# SCX3.net
KiCad netlist of a schematic drawn in EAGLE
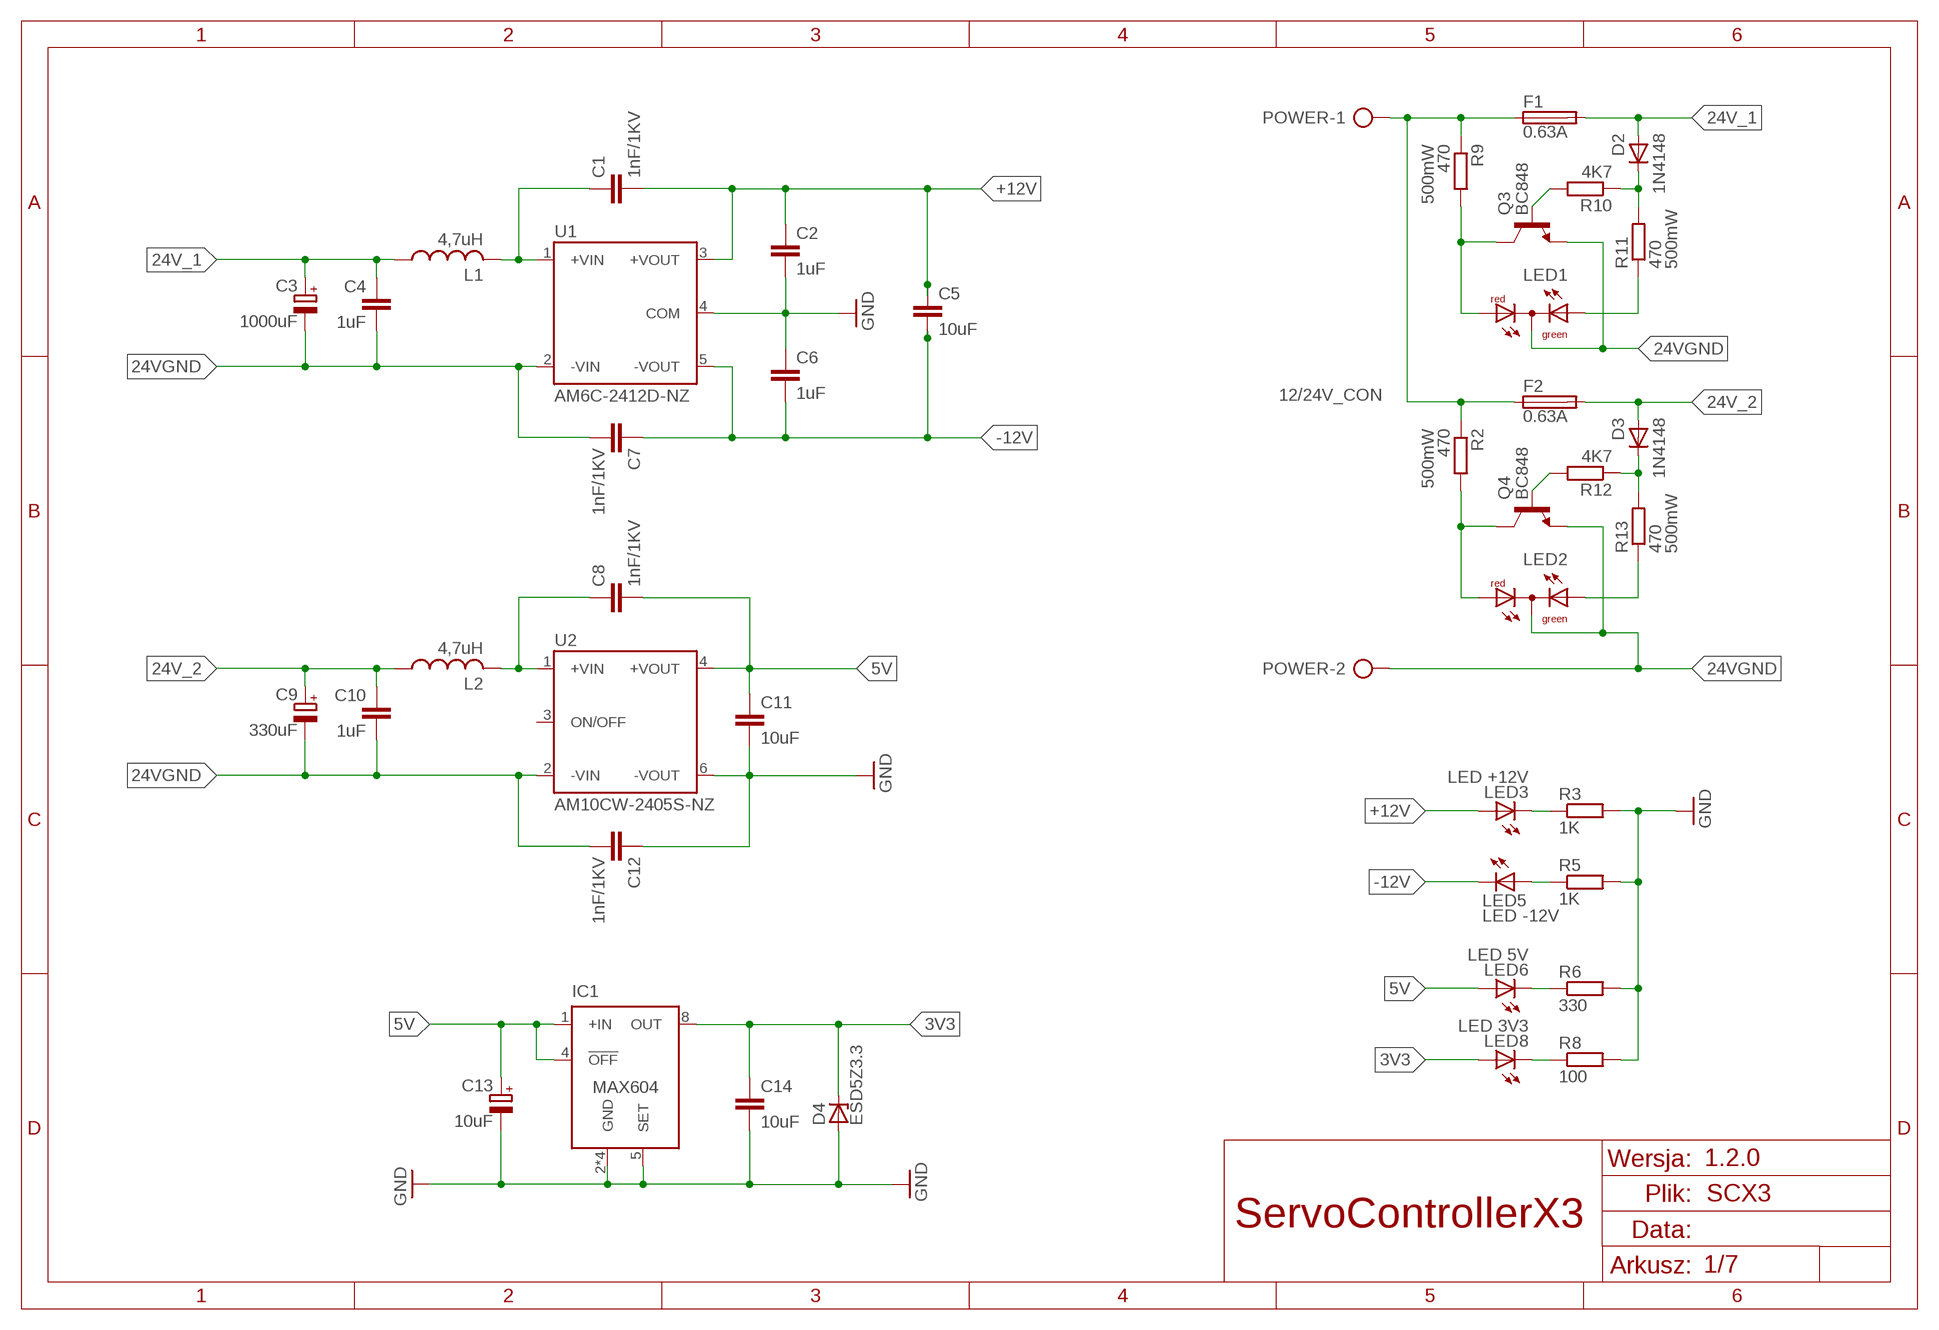
[diagram p0: schematic, sheet 1]
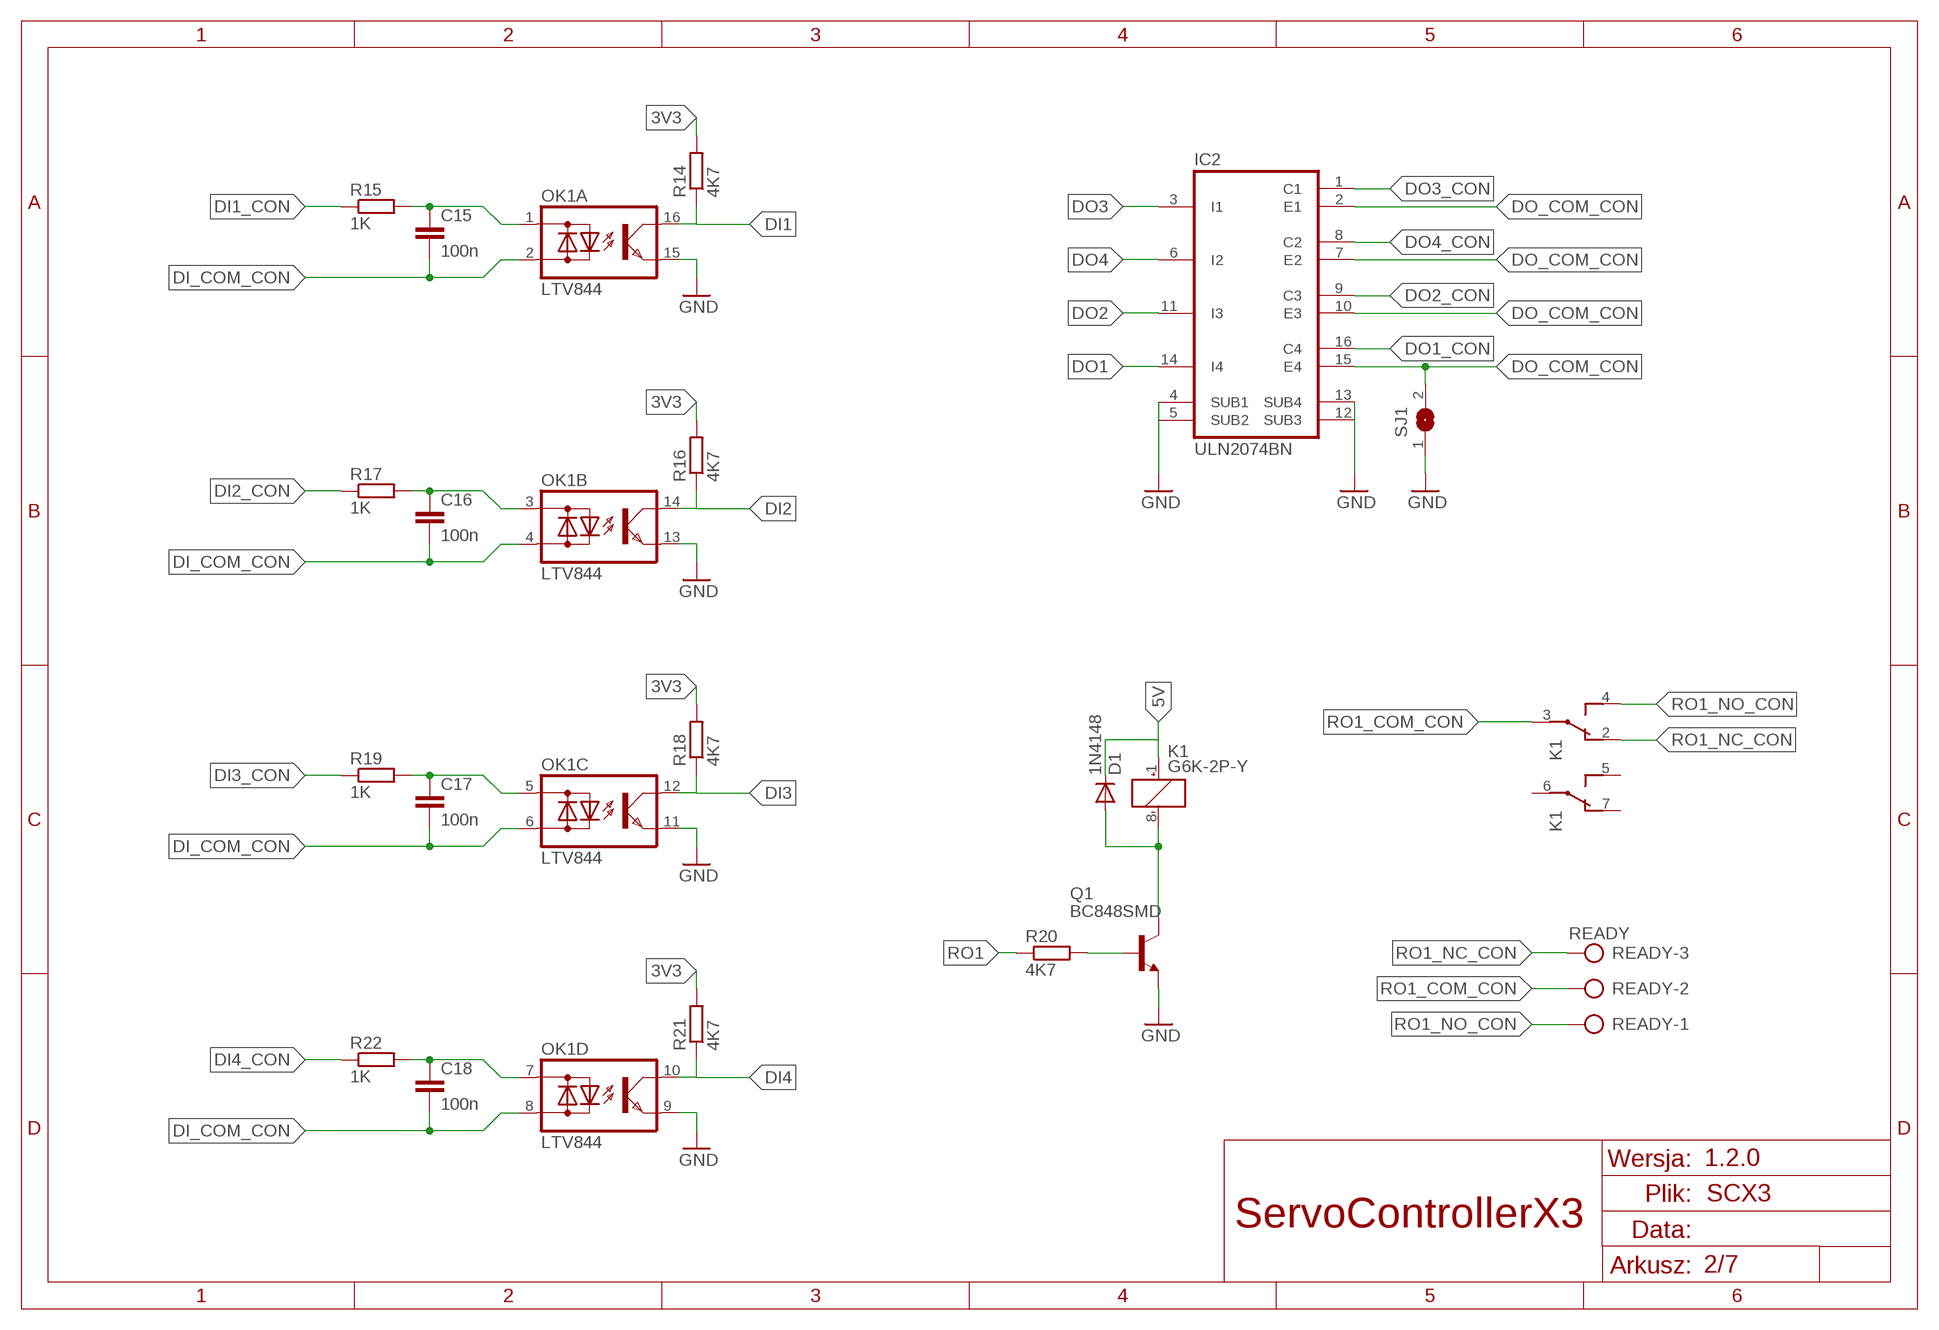
[diagram p1: schematic, sheet 2]
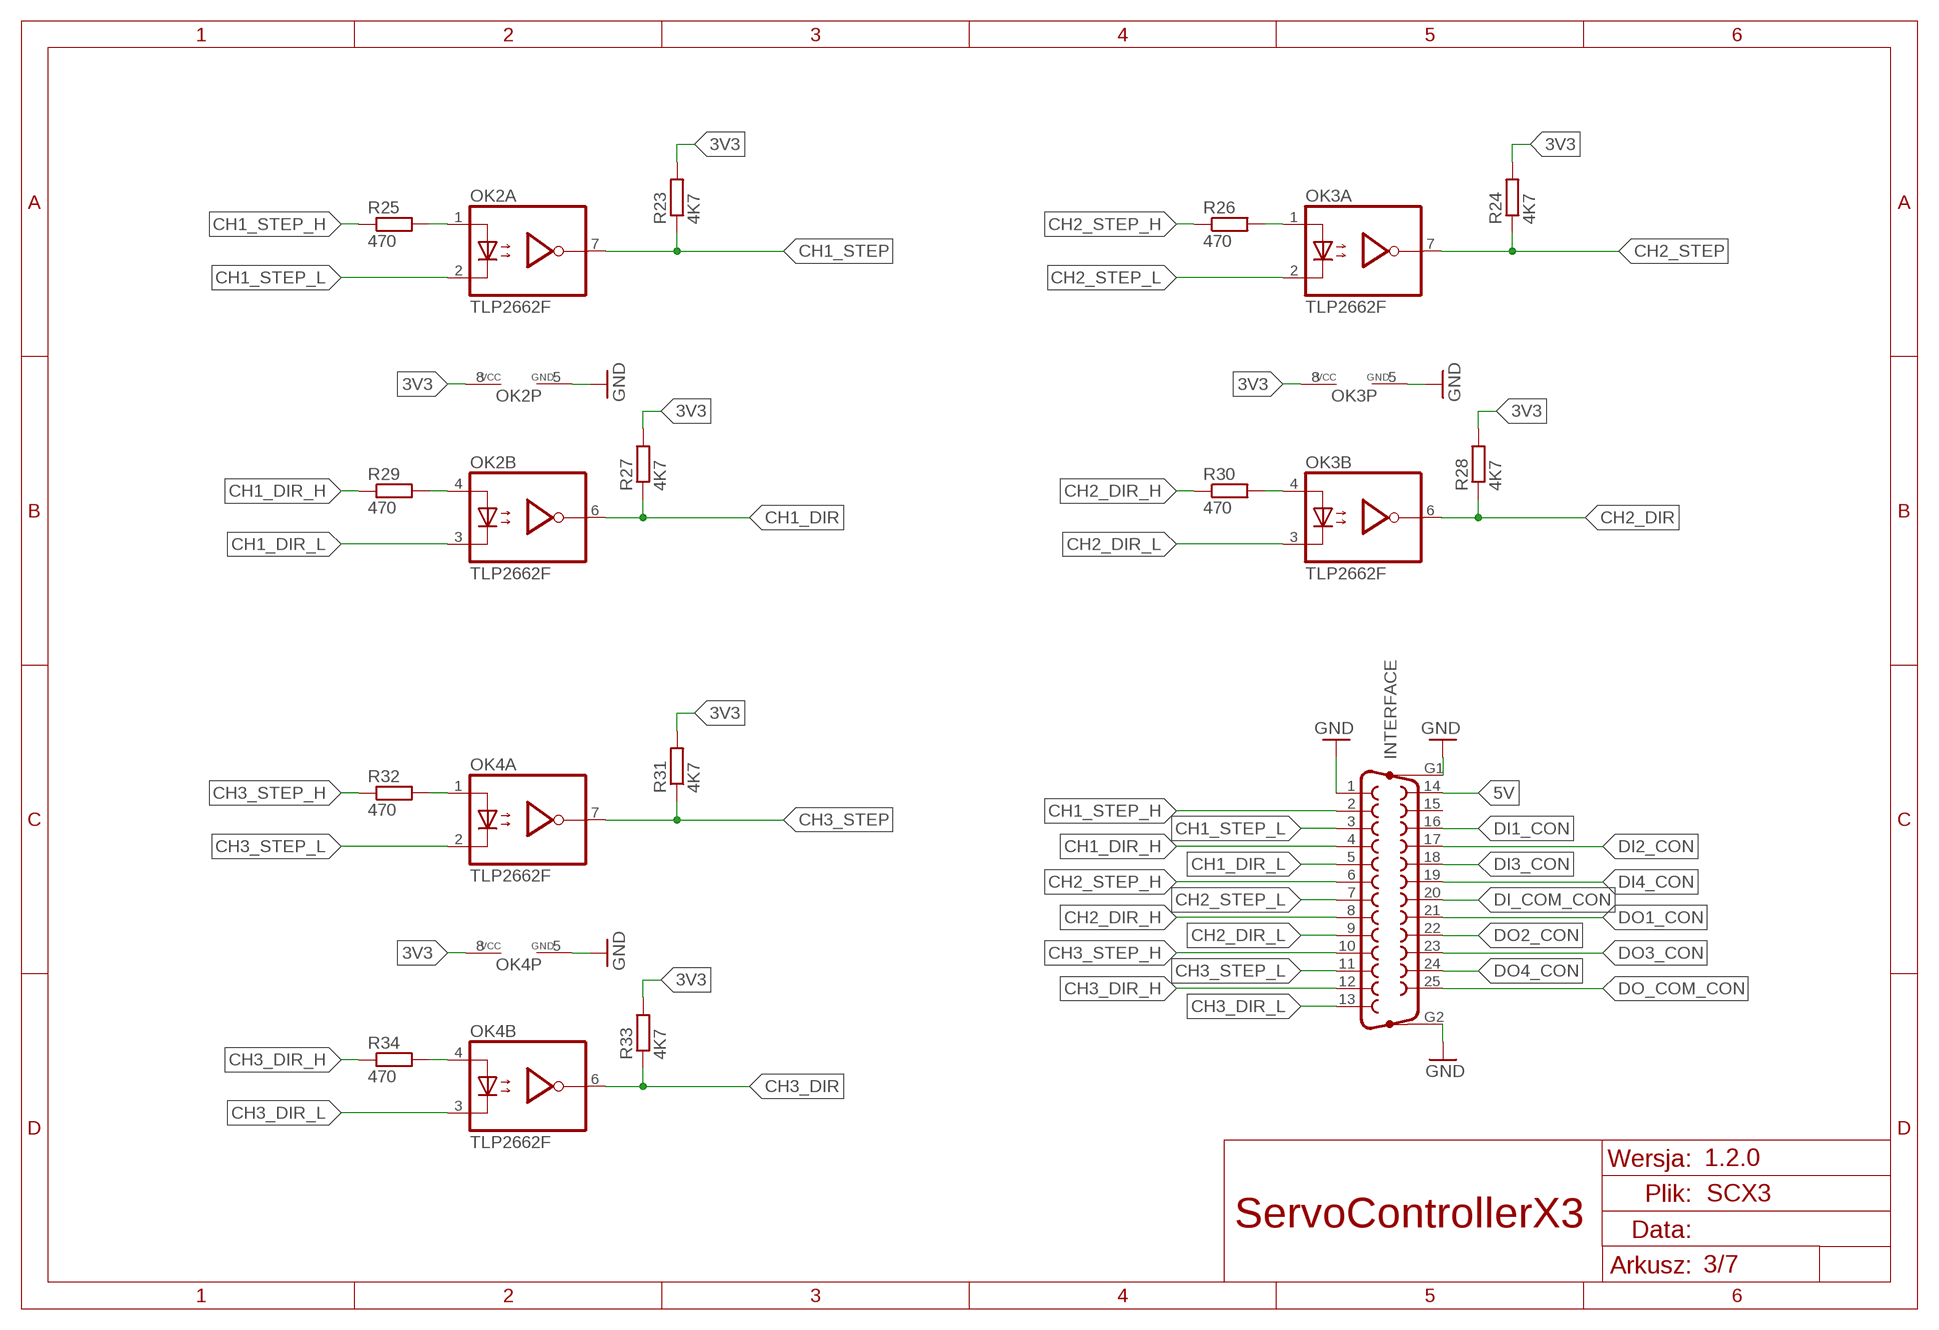
[diagram p2: schematic, sheet 3]
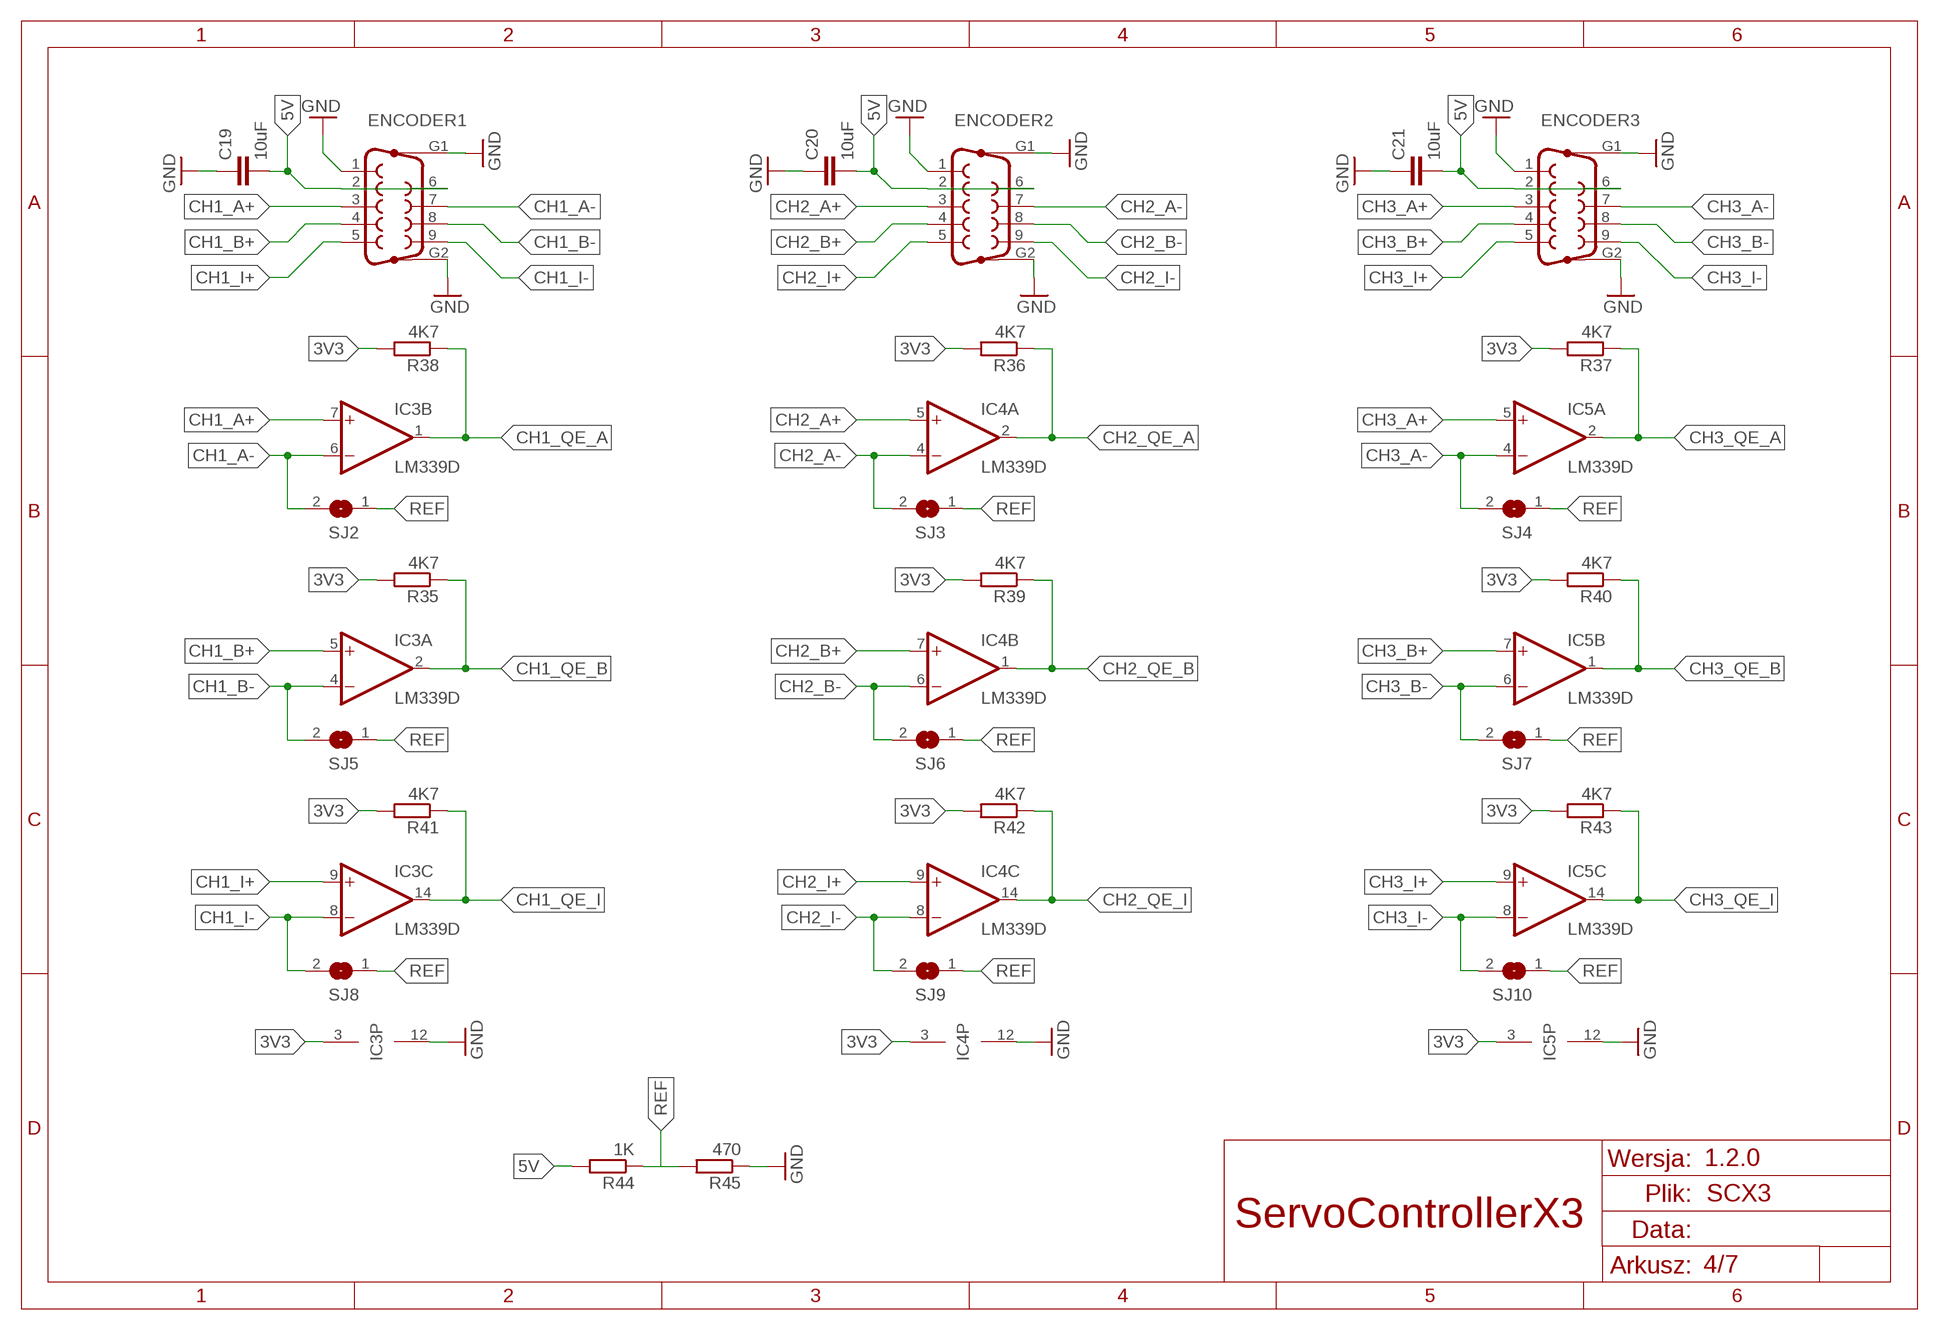
[diagram p3: schematic, sheet 4]
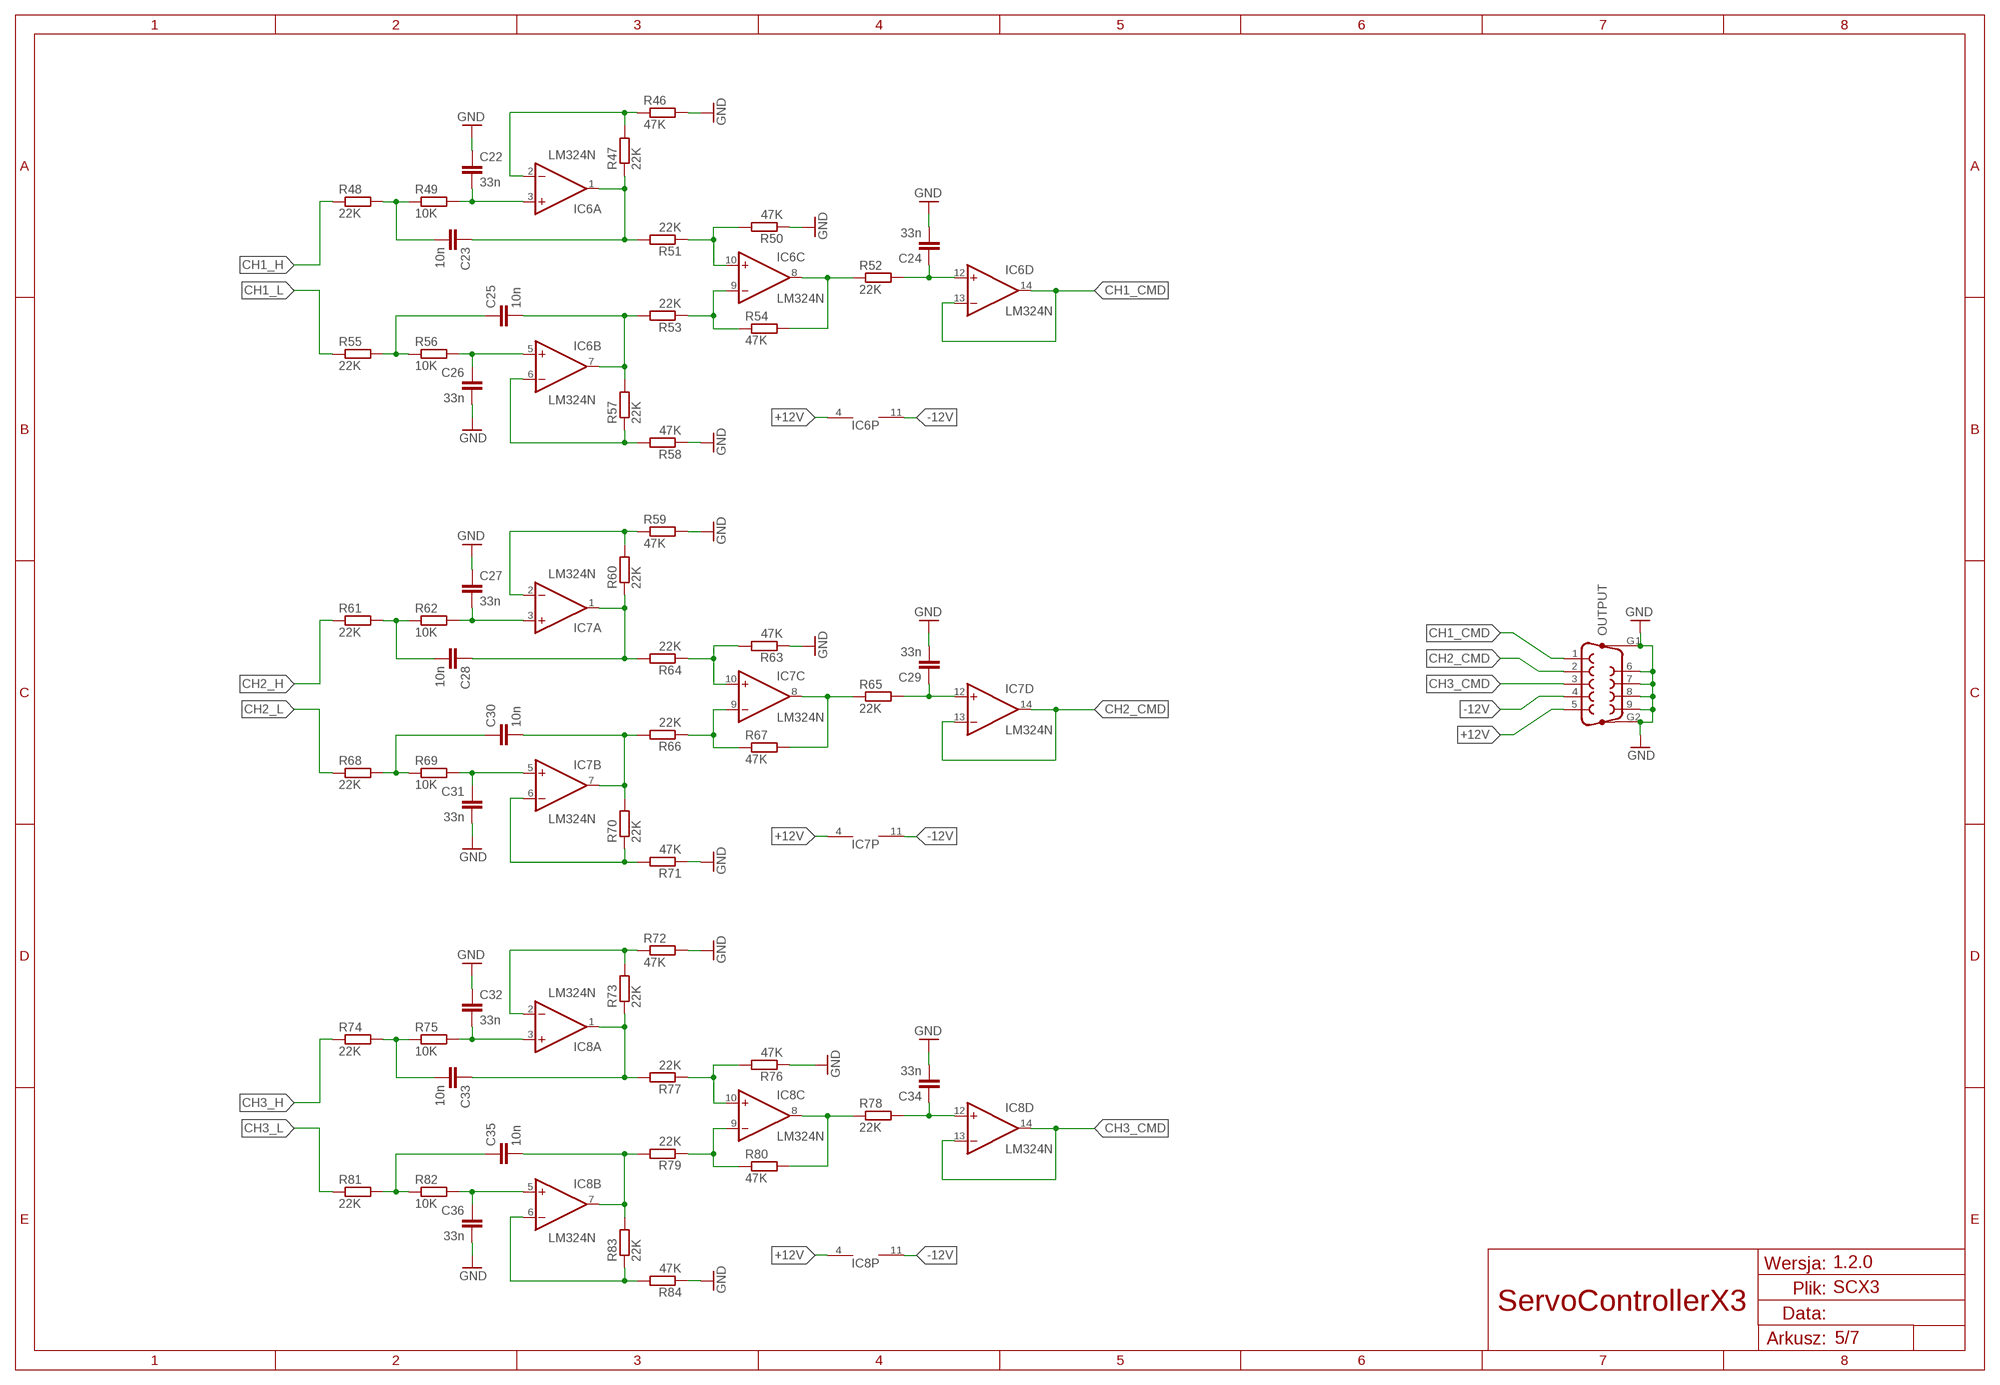
[diagram p4: schematic, sheet 5]
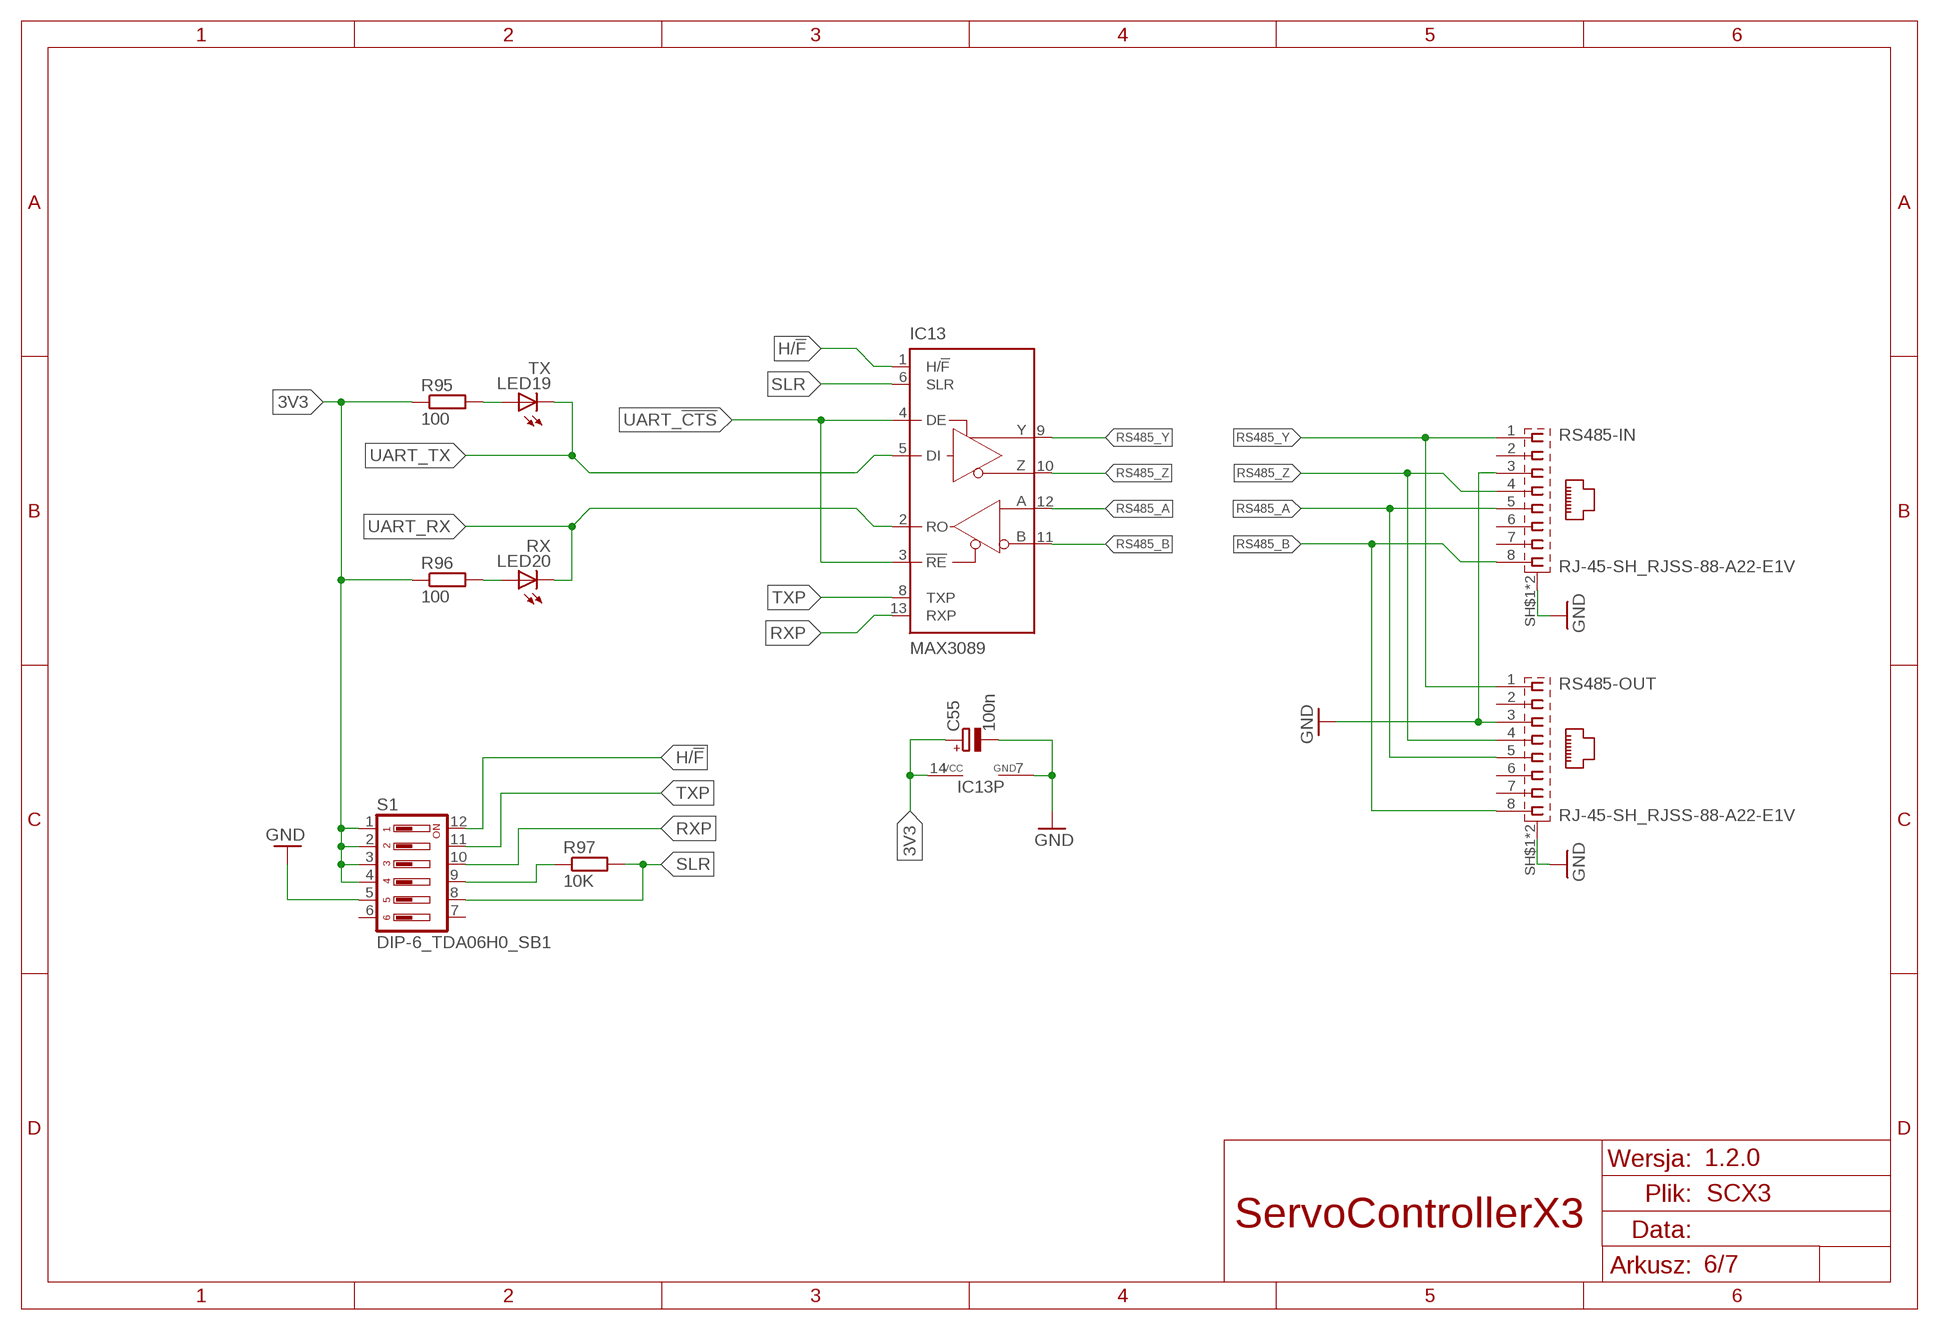
[diagram p5: schematic, sheet 6]
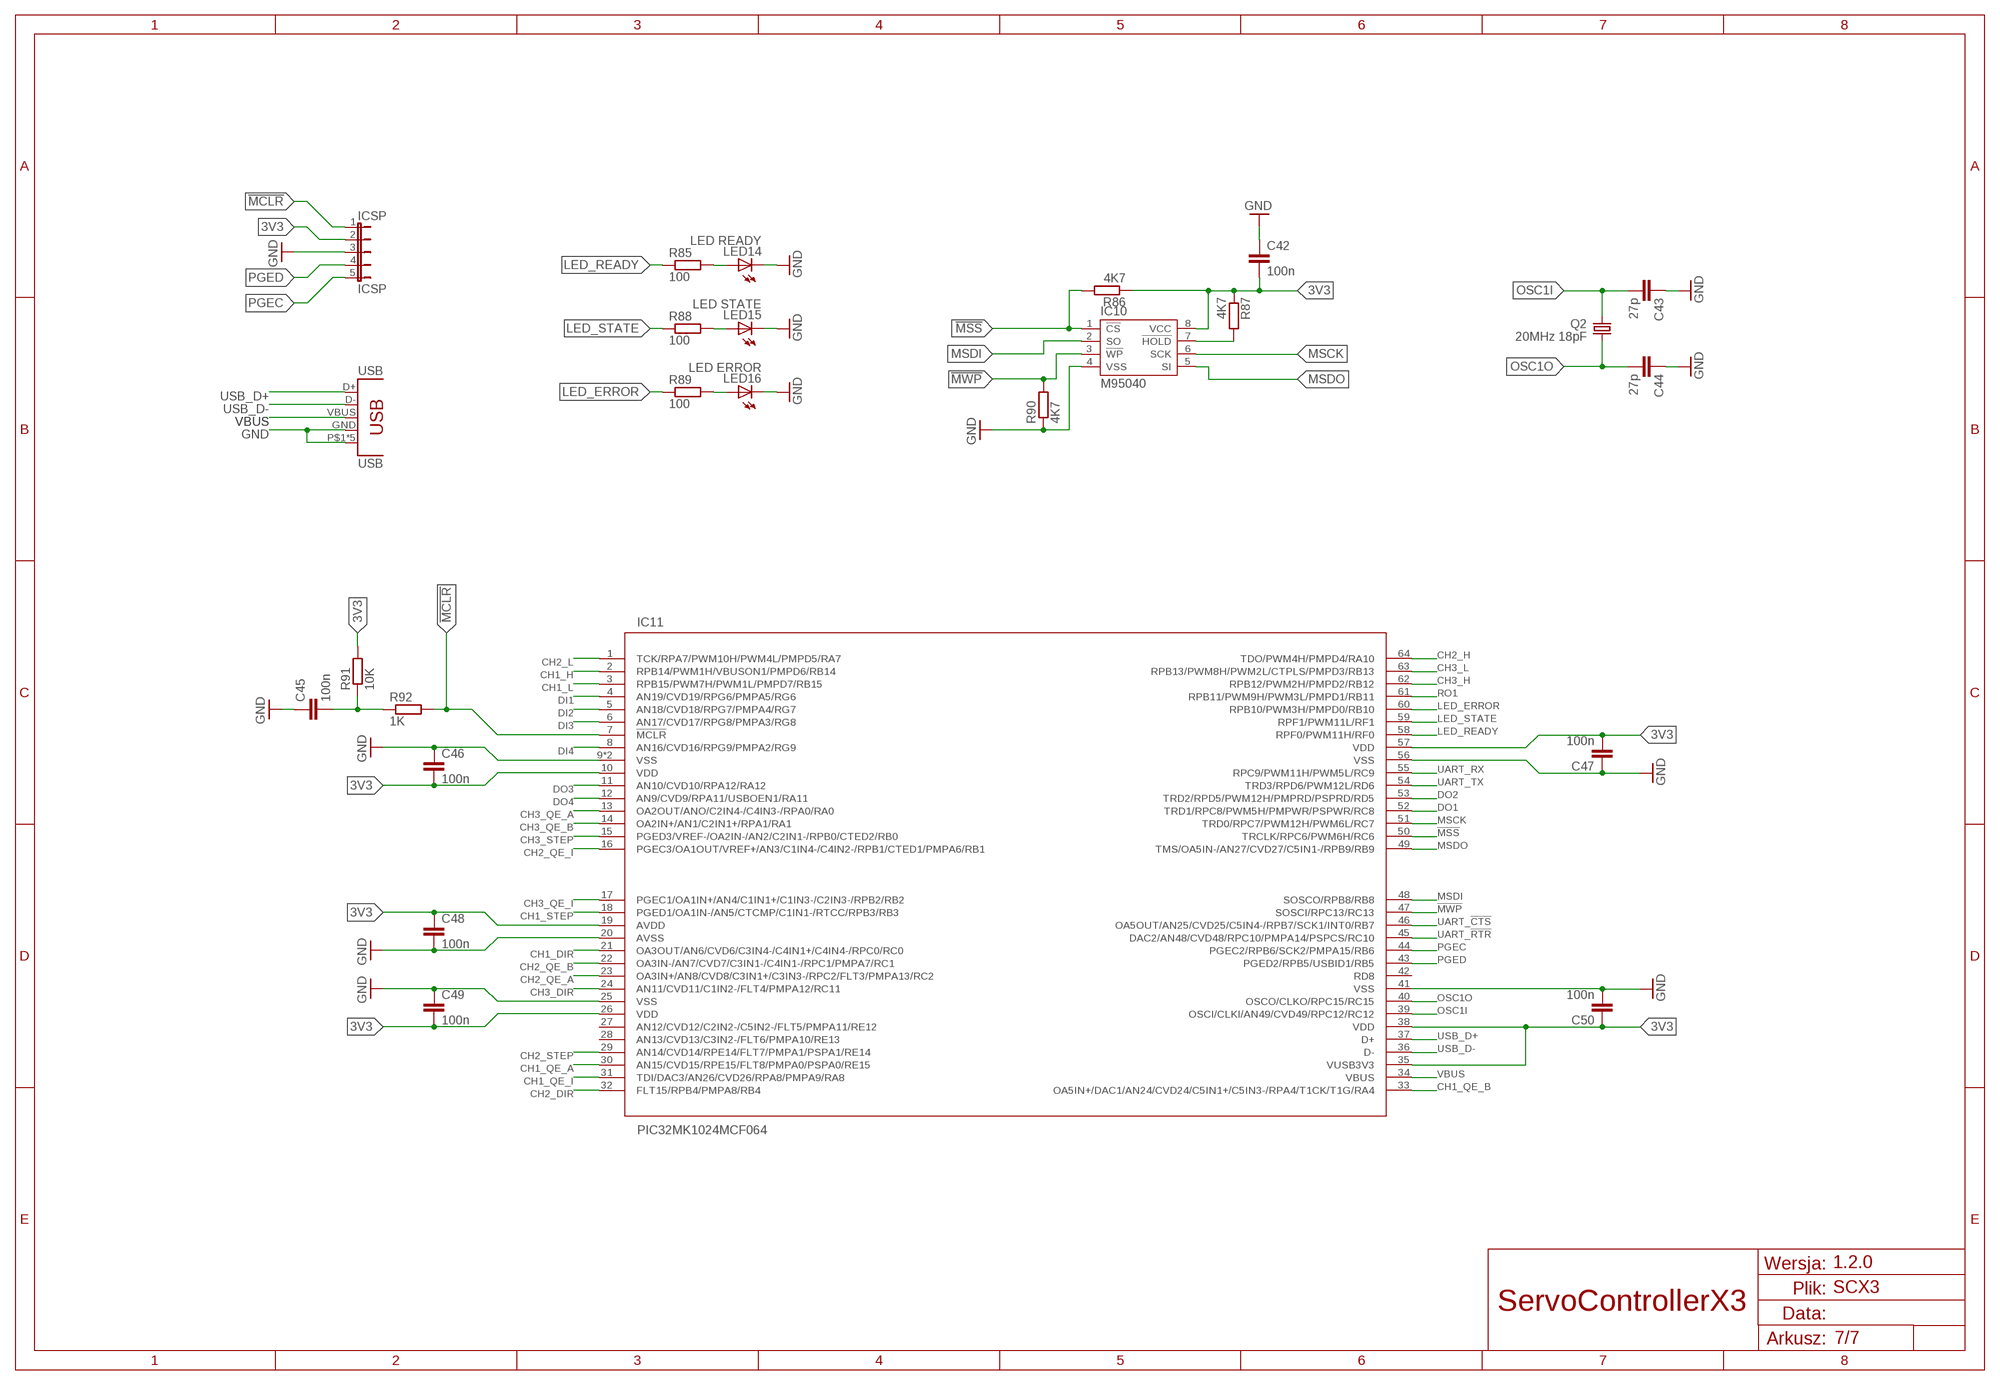
[diagram p6: schematic, sheet 7]

(export (version "E")
  (design (tool "Eeschema 10.0.6"))
  (components
    (comp (ref "C42")
      (value "100n")
      (footprint "eagle-import:C0805")
      (libsource (lib "eagle-import") (part "C-EUC0805"))
    )
    (comp (ref "C43")
      (value "27p")
      (footprint "eagle-import:C0805")
      (libsource (lib "eagle-import") (part "C-EUC0805"))
    )
    (comp (ref "C44")
      (value "27p")
      (footprint "eagle-import:C0805")
      (libsource (lib "eagle-import") (part "C-EUC0805"))
    )
    (comp (ref "C45")
      (value "100n")
      (footprint "eagle-import:C0805")
      (libsource (lib "eagle-import") (part "C-EUC0805"))
    )
    (comp (ref "C46")
      (value "100n")
      (footprint "eagle-import:C0805")
      (libsource (lib "eagle-import") (part "C-EUC0805"))
    )
    (comp (ref "C47")
      (value "100n")
      (footprint "eagle-import:C0805")
      (libsource (lib "eagle-import") (part "C-EUC0805"))
    )
    (comp (ref "C48")
      (value "100n")
      (footprint "eagle-import:C0805")
      (libsource (lib "eagle-import") (part "C-EUC0805"))
    )
    (comp (ref "C49")
      (value "100n")
      (footprint "eagle-import:C0805")
      (libsource (lib "eagle-import") (part "C-EUC0805"))
    )
    (comp (ref "C50")
      (value "100n")
      (footprint "eagle-import:C0805")
      (libsource (lib "eagle-import") (part "C-EUC0805"))
    )
    (comp (ref "IC10")
      (value "M95040")
      (footprint "eagle-import:SO8")
      (libsource (lib "eagle-import") (part "M95040"))
    )
    (comp (ref "IC11")
      (value "PIC32MK1024MCF064")
      (footprint "eagle-import:QFN64-9X9")
      (libsource (lib "eagle-import") (part "PIC32MK1024MCF064"))
    )
    (comp (ref "ICSP")
      (value "ICSP")
      (footprint "eagle-import:JP5")
      (libsource (lib "eagle-import") (part "JP5E"))
    )
    (comp (ref "LED14")
      (value "LED READY")
      (footprint "eagle-import:SML1206")
      (libsource (lib "eagle-import") (part "LEDSML1206"))
    )
    (comp (ref "LED15")
      (value "LED STATE")
      (footprint "eagle-import:SML1206")
      (libsource (lib "eagle-import") (part "LEDSML1206"))
    )
    (comp (ref "LED16")
      (value "LED ERROR")
      (footprint "eagle-import:SML1206")
      (libsource (lib "eagle-import") (part "LEDSML1206"))
    )
    (comp (ref "Q2")
      (value "20MHz 18pF")
      (footprint "eagle-import:SM49")
      (libsource (lib "eagle-import") (part "CRYSTALSM49"))
    )
    (comp (ref "R85")
      (value "100")
      (footprint "eagle-import:R0805")
      (libsource (lib "eagle-import") (part "R-EU_R0805"))
    )
    (comp (ref "R86")
      (value "4K7")
      (footprint "eagle-import:R0805")
      (libsource (lib "eagle-import") (part "R-EU_R0805"))
    )
    (comp (ref "R87")
      (value "4K7")
      (footprint "eagle-import:R0805")
      (libsource (lib "eagle-import") (part "R-EU_R0805"))
    )
    (comp (ref "R88")
      (value "100")
      (footprint "eagle-import:R0805")
      (libsource (lib "eagle-import") (part "R-EU_R0805"))
    )
    (comp (ref "R89")
      (value "100")
      (footprint "eagle-import:R0805")
      (libsource (lib "eagle-import") (part "R-EU_R0805"))
    )
    (comp (ref "R90")
      (value "4K7")
      (footprint "eagle-import:R0805")
      (libsource (lib "eagle-import") (part "R-EU_R0805"))
    )
    (comp (ref "R91")
      (value "10K")
      (footprint "eagle-import:R0805")
      (libsource (lib "eagle-import") (part "R-EU_R0805"))
    )
    (comp (ref "R92")
      (value "1K")
      (footprint "eagle-import:R0805")
      (libsource (lib "eagle-import") (part "R-EU_R0805"))
    )
    (comp (ref "USB")
      (value "USB")
      (footprint "eagle-import:USB-B-PTH-VERTICAL")
      (libsource (lib "eagle-import") (part "DIP-USB-B-TYPE-FMAL(4+2P-2.5-90D)"))
    )
    (comp (ref "C55")
      (value "100n")
      (footprint "eagle-import:UD-4X5,8_NICHICON")
      (libsource (lib "eagle-import") (part "CPOL-EUUD-4X5,8"))
    )
    (comp (ref "IC13")
      (value "MAX3089")
      (footprint "eagle-import:SO14")
      (libsource (lib "eagle-import") (part "MAX3089"))
    )
    (comp (ref "LED19")
      (value "TX")
      (footprint "eagle-import:SML0603")
      (libsource (lib "eagle-import") (part "LEDSML0603"))
    )
    (comp (ref "LED20")
      (value "RX")
      (footprint "eagle-import:SML0603")
      (libsource (lib "eagle-import") (part "LEDSML0603"))
    )
    (comp (ref "R95")
      (value "100")
      (footprint "eagle-import:R0603")
      (libsource (lib "eagle-import") (part "R-EU_R0603"))
    )
    (comp (ref "R96")
      (value "100")
      (footprint "eagle-import:R0603")
      (libsource (lib "eagle-import") (part "R-EU_R0603"))
    )
    (comp (ref "R97")
      (value "10K")
      (footprint "eagle-import:R0603")
      (libsource (lib "eagle-import") (part "R-EU_R0603"))
    )
    (comp (ref "RS485-IN")
      (value "RJ-45-SH_RJSS-88-A22-E1V")
      (footprint "eagle-import:RJ-45M")
      (libsource (lib "eagle-import") (part "RJ-45-SH_RJSS-88-A22-E1V"))
    )
    (comp (ref "RS485-OUT")
      (value "RJ-45-SH_RJSS-88-A22-E1V")
      (footprint "eagle-import:RJ-45M")
      (libsource (lib "eagle-import") (part "RJ-45-SH_RJSS-88-A22-E1V"))
    )
    (comp (ref "S1")
      (value "DIP-6_TDA06H0_SB1")
      (footprint "eagle-import:TDA06H0_S")
      (libsource (lib "eagle-import") (part "DIP-6_SB1_TDA06H0"))
    )
    (comp (ref "C19")
      (value "10uF")
      (footprint "eagle-import:C0805")
      (libsource (lib "eagle-import") (part "C-EUC0805"))
    )
    (comp (ref "C20")
      (value "10uF")
      (footprint "eagle-import:C0805")
      (libsource (lib "eagle-import") (part "C-EUC0805"))
    )
    (comp (ref "C21")
      (value "10uF")
      (footprint "eagle-import:C0805")
      (libsource (lib "eagle-import") (part "C-EUC0805"))
    )
    (comp (ref "ENCODER1")
      (value "F09VP")
      (footprint "eagle-import:F09VP")
      (libsource (lib "eagle-import") (part "F09VP"))
    )
    (comp (ref "ENCODER2")
      (value "F09VP")
      (footprint "eagle-import:F09VP")
      (libsource (lib "eagle-import") (part "F09VP"))
    )
    (comp (ref "ENCODER3")
      (value "F09VP")
      (footprint "eagle-import:F09VP")
      (libsource (lib "eagle-import") (part "F09VP"))
    )
    (comp (ref "IC3")
      (value "LM339D")
      (footprint "eagle-import:SO14")
      (libsource (lib "eagle-import") (part "LM339D"))
    )
    (comp (ref "IC4")
      (value "LM339D")
      (footprint "eagle-import:SO14")
      (libsource (lib "eagle-import") (part "LM339D"))
    )
    (comp (ref "IC5")
      (value "LM339D")
      (footprint "eagle-import:SO14")
      (libsource (lib "eagle-import") (part "LM339D"))
    )
    (comp (ref "R35")
      (value "4K7")
      (footprint "eagle-import:R0805")
      (libsource (lib "eagle-import") (part "R-EU_R0805"))
    )
    (comp (ref "R36")
      (value "4K7")
      (footprint "eagle-import:R0805")
      (libsource (lib "eagle-import") (part "R-EU_R0805"))
    )
    (comp (ref "R37")
      (value "4K7")
      (footprint "eagle-import:R0805")
      (libsource (lib "eagle-import") (part "R-EU_R0805"))
    )
    (comp (ref "R38")
      (value "4K7")
      (footprint "eagle-import:R0805")
      (libsource (lib "eagle-import") (part "R-EU_R0805"))
    )
    (comp (ref "R39")
      (value "4K7")
      (footprint "eagle-import:R0805")
      (libsource (lib "eagle-import") (part "R-EU_R0805"))
    )
    (comp (ref "R40")
      (value "4K7")
      (footprint "eagle-import:R0805")
      (libsource (lib "eagle-import") (part "R-EU_R0805"))
    )
    (comp (ref "R41")
      (value "4K7")
      (footprint "eagle-import:R0805")
      (libsource (lib "eagle-import") (part "R-EU_R0805"))
    )
    (comp (ref "R42")
      (value "4K7")
      (footprint "eagle-import:R0805")
      (libsource (lib "eagle-import") (part "R-EU_R0805"))
    )
    (comp (ref "R43")
      (value "4K7")
      (footprint "eagle-import:R0805")
      (libsource (lib "eagle-import") (part "R-EU_R0805"))
    )
    (comp (ref "R44")
      (value "1K")
      (footprint "eagle-import:R0805")
      (libsource (lib "eagle-import") (part "R-EU_R0805"))
    )
    (comp (ref "R45")
      (value "470")
      (footprint "eagle-import:R0805")
      (libsource (lib "eagle-import") (part "R-EU_R0805"))
    )
    (comp (ref "SJ2") (value "SJ") (footprint "eagle-import:SJ") (libsource (lib "eagle-import") (part "SJ")))
    (comp (ref "SJ3") (value "SJ") (footprint "eagle-import:SJ") (libsource (lib "eagle-import") (part "SJ")))
    (comp (ref "SJ4") (value "SJ") (footprint "eagle-import:SJ") (libsource (lib "eagle-import") (part "SJ")))
    (comp (ref "SJ5") (value "SJ") (footprint "eagle-import:SJ") (libsource (lib "eagle-import") (part "SJ")))
    (comp (ref "SJ6") (value "SJ") (footprint "eagle-import:SJ") (libsource (lib "eagle-import") (part "SJ")))
    (comp (ref "SJ7") (value "SJ") (footprint "eagle-import:SJ") (libsource (lib "eagle-import") (part "SJ")))
    (comp (ref "SJ8") (value "SJ") (footprint "eagle-import:SJ") (libsource (lib "eagle-import") (part "SJ")))
    (comp (ref "SJ9") (value "SJ") (footprint "eagle-import:SJ") (libsource (lib "eagle-import") (part "SJ")))
    (comp (ref "SJ10")
      (value "SJ")
      (footprint "eagle-import:SJ")
      (libsource (lib "eagle-import") (part "SJ"))
    )
    (comp (ref "C1")
      (value "1nF/1KV")
      (footprint "eagle-import:C1206")
      (libsource (lib "eagle-import") (part "C-EUC1206"))
    )
    (comp (ref "C2")
      (value "1uF")
      (footprint "eagle-import:C0805")
      (libsource (lib "eagle-import") (part "C-EUC0805"))
    )
    (comp (ref "C3")
      (value "1000uF")
      (footprint "eagle-import:E5-10,5")
      (libsource (lib "eagle-import") (part "CPOL-EUE5-10.5"))
    )
    (comp (ref "C4")
      (value "1uF")
      (footprint "eagle-import:C0805")
      (libsource (lib "eagle-import") (part "C-EUC0805"))
    )
    (comp (ref "C5")
      (value "10uF")
      (footprint "eagle-import:C0805")
      (libsource (lib "eagle-import") (part "C-EUC0805"))
    )
    (comp (ref "C6")
      (value "1uF")
      (footprint "eagle-import:C0805")
      (libsource (lib "eagle-import") (part "C-EUC0805"))
    )
    (comp (ref "C7")
      (value "1nF/1KV")
      (footprint "eagle-import:C1206")
      (libsource (lib "eagle-import") (part "C-EUC1206"))
    )
    (comp (ref "C8")
      (value "1nF/1KV")
      (footprint "eagle-import:C1206")
      (libsource (lib "eagle-import") (part "C-EUC1206"))
    )
    (comp (ref "C9")
      (value "330uF")
      (footprint "eagle-import:E5-10,5")
      (libsource (lib "eagle-import") (part "CPOL-EUE5-10.5"))
    )
    (comp (ref "C10")
      (value "1uF")
      (footprint "eagle-import:C0805")
      (libsource (lib "eagle-import") (part "C-EUC0805"))
    )
    (comp (ref "C11")
      (value "10uF")
      (footprint "eagle-import:C0805")
      (libsource (lib "eagle-import") (part "C-EUC0805"))
    )
    (comp (ref "C12")
      (value "1nF/1KV")
      (footprint "eagle-import:C1206")
      (libsource (lib "eagle-import") (part "C-EUC1206"))
    )
    (comp (ref "C13")
      (value "10uF")
      (footprint "eagle-import:UD-4X5,8_NICHICON")
      (libsource (lib "eagle-import") (part "CPOL-EUUD-4X5,8"))
    )
    (comp (ref "C14")
      (value "10uF")
      (footprint "eagle-import:C0805")
      (libsource (lib "eagle-import") (part "C-EUC0805"))
    )
    (comp (ref "D2")
      (value "1N4148")
      (footprint "eagle-import:D0805")
      (libsource (lib "eagle-import") (part "1N4148SMD-0805"))
    )
    (comp (ref "D3")
      (value "1N4148")
      (footprint "eagle-import:D0805")
      (libsource (lib "eagle-import") (part "1N4148SMD-0805"))
    )
    (comp (ref "D4")
      (value "ESD5Z3.3")
      (footprint "eagle-import:SOD523")
      (libsource (lib "eagle-import") (part "ZENER-DIODESOD523"))
    )
    (comp (ref "F1")
      (value "0.63A")
      (footprint "eagle-import:TR5")
      (libsource (lib "eagle-import") (part "TR5"))
    )
    (comp (ref "F2")
      (value "0.63A")
      (footprint "eagle-import:TR5")
      (libsource (lib "eagle-import") (part "TR5"))
    )
    (comp (ref "IC1")
      (value "MAX604")
      (footprint "eagle-import:DIL08")
      (libsource (lib "eagle-import") (part "MAX604"))
    )
    (comp (ref "L1")
      (value "4,7uH")
      (footprint "eagle-import:DJNR6028")
      (libsource (lib "eagle-import") (part "DJNR6028--S"))
    )
    (comp (ref "L2")
      (value "4,7uH")
      (footprint "eagle-import:DJNR6028")
      (libsource (lib "eagle-import") (part "DJNR6028--S"))
    )
    (comp (ref "LED1")
      (value "DUOLED-RG-C")
      (footprint "eagle-import:DUOLED-C-5MM")
      (libsource (lib "eagle-import") (part "DUOLED-RG-C"))
    )
    (comp (ref "LED2")
      (value "DUOLED-RG-C")
      (footprint "eagle-import:DUOLED-C-5MM")
      (libsource (lib "eagle-import") (part "DUOLED-RG-C"))
    )
    (comp (ref "LED3")
      (value "LED +12V")
      (footprint "eagle-import:SML1206")
      (libsource (lib "eagle-import") (part "LEDSML1206"))
    )
    (comp (ref "LED5")
      (value "LED -12V")
      (footprint "eagle-import:SML1206")
      (libsource (lib "eagle-import") (part "LEDSML1206"))
    )
    (comp (ref "LED6")
      (value "LED 5V")
      (footprint "eagle-import:SML1206")
      (libsource (lib "eagle-import") (part "LEDSML1206"))
    )
    (comp (ref "LED8")
      (value "LED 3V3")
      (footprint "eagle-import:SML1206")
      (libsource (lib "eagle-import") (part "LEDSML1206"))
    )
    (comp (ref "POWER")
      (value "12/24V_CON")
      (footprint "eagle-import:AK500_2")
      (libsource (lib "eagle-import") (part "AK500/2"))
    )
    (comp (ref "Q3")
      (value "BC848")
      (footprint "eagle-import:SOT23")
      (libsource (lib "eagle-import") (part "BC848SMD"))
    )
    (comp (ref "Q4")
      (value "BC848")
      (footprint "eagle-import:SOT23")
      (libsource (lib "eagle-import") (part "BC848SMD"))
    )
    (comp (ref "R2")
      (value "470")
      (footprint "eagle-import:R1206")
      (fields (field (name "WATTAGE") "500mW"))
      (libsource (lib "eagle-import") (part "R-EU_R1206"))
    )
    (comp (ref "R3")
      (value "1K")
      (footprint "eagle-import:R0805")
      (libsource (lib "eagle-import") (part "R-EU_R0805"))
    )
    (comp (ref "R5")
      (value "1K")
      (footprint "eagle-import:R0805")
      (libsource (lib "eagle-import") (part "R-EU_R0805"))
    )
    (comp (ref "R6")
      (value "330")
      (footprint "eagle-import:R0805")
      (libsource (lib "eagle-import") (part "R-EU_R0805"))
    )
    (comp (ref "R8")
      (value "100")
      (footprint "eagle-import:R0805")
      (libsource (lib "eagle-import") (part "R-EU_R0805"))
    )
    (comp (ref "R9")
      (value "470")
      (footprint "eagle-import:R1206")
      (fields (field (name "WATTAGE") "500mW"))
      (libsource (lib "eagle-import") (part "R-EU_R1206"))
    )
    (comp (ref "R10")
      (value "4K7")
      (footprint "eagle-import:R0805")
      (libsource (lib "eagle-import") (part "R-EU_R0805"))
    )
    (comp (ref "R11")
      (value "470")
      (footprint "eagle-import:R1206")
      (fields (field (name "WATTAGE") "500mW"))
      (libsource (lib "eagle-import") (part "R-EU_R1206"))
    )
    (comp (ref "R12")
      (value "4K7")
      (footprint "eagle-import:R0805")
      (libsource (lib "eagle-import") (part "R-EU_R0805"))
    )
    (comp (ref "R13")
      (value "470")
      (footprint "eagle-import:R1206")
      (fields (field (name "WATTAGE") "500mW"))
      (libsource (lib "eagle-import") (part "R-EU_R1206"))
    )
    (comp (ref "U1")
      (value "AM6C-2412D-NZ")
      (footprint "eagle-import:AM6C")
      (libsource (lib "eagle-import") (part "AM6C-D-NZ2412"))
    )
    (comp (ref "U2")
      (value "AM10CW-2405S-NZ")
      (footprint "eagle-import:AM10CW-NZ")
      (libsource (lib "eagle-import") (part "AM10CW-S-NZ2405"))
    )
    (comp (ref "C22")
      (value "33n")
      (footprint "eagle-import:C0805")
      (libsource (lib "eagle-import") (part "C-EUC0805"))
    )
    (comp (ref "C23")
      (value "10n")
      (footprint "eagle-import:C0805")
      (libsource (lib "eagle-import") (part "C-EUC0805"))
    )
    (comp (ref "C24")
      (value "33n")
      (footprint "eagle-import:C0805")
      (libsource (lib "eagle-import") (part "C-EUC0805"))
    )
    (comp (ref "C25")
      (value "10n")
      (footprint "eagle-import:C0805")
      (libsource (lib "eagle-import") (part "C-EUC0805"))
    )
    (comp (ref "C26")
      (value "33n")
      (footprint "eagle-import:C0805")
      (libsource (lib "eagle-import") (part "C-EUC0805"))
    )
    (comp (ref "C27")
      (value "33n")
      (footprint "eagle-import:C0805")
      (libsource (lib "eagle-import") (part "C-EUC0805"))
    )
    (comp (ref "C28")
      (value "10n")
      (footprint "eagle-import:C0805")
      (libsource (lib "eagle-import") (part "C-EUC0805"))
    )
    (comp (ref "C29")
      (value "33n")
      (footprint "eagle-import:C0805")
      (libsource (lib "eagle-import") (part "C-EUC0805"))
    )
    (comp (ref "C30")
      (value "10n")
      (footprint "eagle-import:C0805")
      (libsource (lib "eagle-import") (part "C-EUC0805"))
    )
    (comp (ref "C31")
      (value "33n")
      (footprint "eagle-import:C0805")
      (libsource (lib "eagle-import") (part "C-EUC0805"))
    )
    (comp (ref "C32")
      (value "33n")
      (footprint "eagle-import:C0805")
      (libsource (lib "eagle-import") (part "C-EUC0805"))
    )
    (comp (ref "C33")
      (value "10n")
      (footprint "eagle-import:C0805")
      (libsource (lib "eagle-import") (part "C-EUC0805"))
    )
    (comp (ref "C34")
      (value "33n")
      (footprint "eagle-import:C0805")
      (libsource (lib "eagle-import") (part "C-EUC0805"))
    )
    (comp (ref "C35")
      (value "10n")
      (footprint "eagle-import:C0805")
      (libsource (lib "eagle-import") (part "C-EUC0805"))
    )
    (comp (ref "C36")
      (value "33n")
      (footprint "eagle-import:C0805")
      (libsource (lib "eagle-import") (part "C-EUC0805"))
    )
    (comp (ref "IC6")
      (value "LM324N")
      (footprint "eagle-import:DIL14")
      (libsource (lib "eagle-import") (part "LM324N"))
    )
    (comp (ref "IC7")
      (value "LM324N")
      (footprint "eagle-import:DIL14")
      (libsource (lib "eagle-import") (part "LM324N"))
    )
    (comp (ref "IC8")
      (value "LM324N")
      (footprint "eagle-import:DIL14")
      (libsource (lib "eagle-import") (part "LM324N"))
    )
    (comp (ref "OUTPUT")
      (value "F09VP")
      (footprint "eagle-import:F09VP")
      (libsource (lib "eagle-import") (part "F09VP"))
    )
    (comp (ref "R46")
      (value "47K")
      (footprint "eagle-import:R0805")
      (libsource (lib "eagle-import") (part "R-EU_R0805"))
    )
    (comp (ref "R47")
      (value "22K")
      (footprint "eagle-import:R0805")
      (libsource (lib "eagle-import") (part "R-EU_R0805"))
    )
    (comp (ref "R48")
      (value "22K")
      (footprint "eagle-import:R0805")
      (libsource (lib "eagle-import") (part "R-EU_R0805"))
    )
    (comp (ref "R49")
      (value "10K")
      (footprint "eagle-import:R0805")
      (libsource (lib "eagle-import") (part "R-EU_R0805"))
    )
    (comp (ref "R50")
      (value "47K")
      (footprint "eagle-import:R0805")
      (libsource (lib "eagle-import") (part "R-EU_R0805"))
    )
    (comp (ref "R51")
      (value "22K")
      (footprint "eagle-import:R0805")
      (libsource (lib "eagle-import") (part "R-EU_R0805"))
    )
    (comp (ref "R52")
      (value "22K")
      (footprint "eagle-import:R0805")
      (libsource (lib "eagle-import") (part "R-EU_R0805"))
    )
    (comp (ref "R53")
      (value "22K")
      (footprint "eagle-import:R0805")
      (libsource (lib "eagle-import") (part "R-EU_R0805"))
    )
    (comp (ref "R54")
      (value "47K")
      (footprint "eagle-import:R0805")
      (libsource (lib "eagle-import") (part "R-EU_R0805"))
    )
    (comp (ref "R55")
      (value "22K")
      (footprint "eagle-import:R0805")
      (libsource (lib "eagle-import") (part "R-EU_R0805"))
    )
    (comp (ref "R56")
      (value "10K")
      (footprint "eagle-import:R0805")
      (libsource (lib "eagle-import") (part "R-EU_R0805"))
    )
    (comp (ref "R57")
      (value "22K")
      (footprint "eagle-import:R0805")
      (libsource (lib "eagle-import") (part "R-EU_R0805"))
    )
    (comp (ref "R58")
      (value "47K")
      (footprint "eagle-import:R0805")
      (libsource (lib "eagle-import") (part "R-EU_R0805"))
    )
    (comp (ref "R59")
      (value "47K")
      (footprint "eagle-import:R0805")
      (libsource (lib "eagle-import") (part "R-EU_R0805"))
    )
    (comp (ref "R60")
      (value "22K")
      (footprint "eagle-import:R0805")
      (libsource (lib "eagle-import") (part "R-EU_R0805"))
    )
    (comp (ref "R61")
      (value "22K")
      (footprint "eagle-import:R0805")
      (libsource (lib "eagle-import") (part "R-EU_R0805"))
    )
    (comp (ref "R62")
      (value "10K")
      (footprint "eagle-import:R0805")
      (libsource (lib "eagle-import") (part "R-EU_R0805"))
    )
    (comp (ref "R63")
      (value "47K")
      (footprint "eagle-import:R0805")
      (libsource (lib "eagle-import") (part "R-EU_R0805"))
    )
    (comp (ref "R64")
      (value "22K")
      (footprint "eagle-import:R0805")
      (libsource (lib "eagle-import") (part "R-EU_R0805"))
    )
    (comp (ref "R65")
      (value "22K")
      (footprint "eagle-import:R0805")
      (libsource (lib "eagle-import") (part "R-EU_R0805"))
    )
    (comp (ref "R66")
      (value "22K")
      (footprint "eagle-import:R0805")
      (libsource (lib "eagle-import") (part "R-EU_R0805"))
    )
    (comp (ref "R67")
      (value "47K")
      (footprint "eagle-import:R0805")
      (libsource (lib "eagle-import") (part "R-EU_R0805"))
    )
    (comp (ref "R68")
      (value "22K")
      (footprint "eagle-import:R0805")
      (libsource (lib "eagle-import") (part "R-EU_R0805"))
    )
    (comp (ref "R69")
      (value "10K")
      (footprint "eagle-import:R0805")
      (libsource (lib "eagle-import") (part "R-EU_R0805"))
    )
    (comp (ref "R70")
      (value "22K")
      (footprint "eagle-import:R0805")
      (libsource (lib "eagle-import") (part "R-EU_R0805"))
    )
    (comp (ref "R71")
      (value "47K")
      (footprint "eagle-import:R0805")
      (libsource (lib "eagle-import") (part "R-EU_R0805"))
    )
    (comp (ref "R72")
      (value "47K")
      (footprint "eagle-import:R0805")
      (libsource (lib "eagle-import") (part "R-EU_R0805"))
    )
    (comp (ref "R73")
      (value "22K")
      (footprint "eagle-import:R0805")
      (libsource (lib "eagle-import") (part "R-EU_R0805"))
    )
    (comp (ref "R74")
      (value "22K")
      (footprint "eagle-import:R0805")
      (libsource (lib "eagle-import") (part "R-EU_R0805"))
    )
    (comp (ref "R75")
      (value "10K")
      (footprint "eagle-import:R0805")
      (libsource (lib "eagle-import") (part "R-EU_R0805"))
    )
    (comp (ref "R76")
      (value "47K")
      (footprint "eagle-import:R0805")
      (libsource (lib "eagle-import") (part "R-EU_R0805"))
    )
    (comp (ref "R77")
      (value "22K")
      (footprint "eagle-import:R0805")
      (libsource (lib "eagle-import") (part "R-EU_R0805"))
    )
    (comp (ref "R78")
      (value "22K")
      (footprint "eagle-import:R0805")
      (libsource (lib "eagle-import") (part "R-EU_R0805"))
    )
    (comp (ref "R79")
      (value "22K")
      (footprint "eagle-import:R0805")
      (libsource (lib "eagle-import") (part "R-EU_R0805"))
    )
    (comp (ref "R80")
      (value "47K")
      (footprint "eagle-import:R0805")
      (libsource (lib "eagle-import") (part "R-EU_R0805"))
    )
    (comp (ref "R81")
      (value "22K")
      (footprint "eagle-import:R0805")
      (libsource (lib "eagle-import") (part "R-EU_R0805"))
    )
    (comp (ref "R82")
      (value "10K")
      (footprint "eagle-import:R0805")
      (libsource (lib "eagle-import") (part "R-EU_R0805"))
    )
    (comp (ref "R83")
      (value "22K")
      (footprint "eagle-import:R0805")
      (libsource (lib "eagle-import") (part "R-EU_R0805"))
    )
    (comp (ref "R84")
      (value "47K")
      (footprint "eagle-import:R0805")
      (libsource (lib "eagle-import") (part "R-EU_R0805"))
    )
    (comp (ref "INTERFACE")
      (value "F25VP")
      (footprint "eagle-import:F25VP")
      (libsource (lib "eagle-import") (part "F25VP"))
    )
    (comp (ref "OK2")
      (value "TLP2662F")
      (footprint "eagle-import:DIL08")
      (libsource (lib "eagle-import") (part "TLP2662F"))
    )
    (comp (ref "OK3")
      (value "TLP2662F")
      (footprint "eagle-import:DIL08")
      (libsource (lib "eagle-import") (part "TLP2662F"))
    )
    (comp (ref "OK4")
      (value "TLP2662F")
      (footprint "eagle-import:DIL08")
      (libsource (lib "eagle-import") (part "TLP2662F"))
    )
    (comp (ref "R23")
      (value "4K7")
      (footprint "eagle-import:R0805")
      (libsource (lib "eagle-import") (part "R-EU_R0805"))
    )
    (comp (ref "R24")
      (value "4K7")
      (footprint "eagle-import:R0805")
      (libsource (lib "eagle-import") (part "R-EU_R0805"))
    )
    (comp (ref "R25")
      (value "470")
      (footprint "eagle-import:R0805")
      (libsource (lib "eagle-import") (part "R-EU_R0805"))
    )
    (comp (ref "R26")
      (value "470")
      (footprint "eagle-import:R0805")
      (libsource (lib "eagle-import") (part "R-EU_R0805"))
    )
    (comp (ref "R27")
      (value "4K7")
      (footprint "eagle-import:R0805")
      (libsource (lib "eagle-import") (part "R-EU_R0805"))
    )
    (comp (ref "R28")
      (value "4K7")
      (footprint "eagle-import:R0805")
      (libsource (lib "eagle-import") (part "R-EU_R0805"))
    )
    (comp (ref "R29")
      (value "470")
      (footprint "eagle-import:R0805")
      (libsource (lib "eagle-import") (part "R-EU_R0805"))
    )
    (comp (ref "R30")
      (value "470")
      (footprint "eagle-import:R0805")
      (libsource (lib "eagle-import") (part "R-EU_R0805"))
    )
    (comp (ref "R31")
      (value "4K7")
      (footprint "eagle-import:R0805")
      (libsource (lib "eagle-import") (part "R-EU_R0805"))
    )
    (comp (ref "R32")
      (value "470")
      (footprint "eagle-import:R0805")
      (libsource (lib "eagle-import") (part "R-EU_R0805"))
    )
    (comp (ref "R33")
      (value "4K7")
      (footprint "eagle-import:R0805")
      (libsource (lib "eagle-import") (part "R-EU_R0805"))
    )
    (comp (ref "R34")
      (value "470")
      (footprint "eagle-import:R0805")
      (libsource (lib "eagle-import") (part "R-EU_R0805"))
    )
    (comp (ref "C15")
      (value "100n")
      (footprint "eagle-import:C0805")
      (libsource (lib "eagle-import") (part "C-EUC0805"))
    )
    (comp (ref "C16")
      (value "100n")
      (footprint "eagle-import:C0805")
      (libsource (lib "eagle-import") (part "C-EUC0805"))
    )
    (comp (ref "C17")
      (value "100n")
      (footprint "eagle-import:C0805")
      (libsource (lib "eagle-import") (part "C-EUC0805"))
    )
    (comp (ref "C18")
      (value "100n")
      (footprint "eagle-import:C0805")
      (libsource (lib "eagle-import") (part "C-EUC0805"))
    )
    (comp (ref "D1")
      (value "1N4148")
      (footprint "eagle-import:D0805")
      (libsource (lib "eagle-import") (part "1N4148SMD-0805"))
    )
    (comp (ref "IC2")
      (value "ULN2074BN")
      (footprint "eagle-import:DIL16")
      (libsource (lib "eagle-import") (part "ULN2074BN"))
    )
    (comp (ref "K1")
      (value "G6K-2P-Y")
      (footprint "eagle-import:G6K-2P-Y")
      (fields (field (name "MF") "OMRON COMPONENTS USA") (field (name "MPN") "G6K-2P-Y DC12"))
      (libsource (lib "eagle-import") (part "G6K-2P-Y"))
    )
    (comp (ref "OK1")
      (value "LTV844")
      (footprint "eagle-import:DIL16")
      (libsource (lib "eagle-import") (part "LTV844"))
    )
    (comp (ref "Q1")
      (value "BC848SMD")
      (footprint "eagle-import:SOT23")
      (libsource (lib "eagle-import") (part "BC848SMD"))
    )
    (comp (ref "R14")
      (value "4K7")
      (footprint "eagle-import:R0805")
      (libsource (lib "eagle-import") (part "R-EU_R0805"))
    )
    (comp (ref "R15")
      (value "1K")
      (footprint "eagle-import:R0805")
      (libsource (lib "eagle-import") (part "R-EU_R0805"))
    )
    (comp (ref "R16")
      (value "4K7")
      (footprint "eagle-import:R0805")
      (libsource (lib "eagle-import") (part "R-EU_R0805"))
    )
    (comp (ref "R17")
      (value "1K")
      (footprint "eagle-import:R0805")
      (libsource (lib "eagle-import") (part "R-EU_R0805"))
    )
    (comp (ref "R18")
      (value "4K7")
      (footprint "eagle-import:R0805")
      (libsource (lib "eagle-import") (part "R-EU_R0805"))
    )
    (comp (ref "R19")
      (value "1K")
      (footprint "eagle-import:R0805")
      (libsource (lib "eagle-import") (part "R-EU_R0805"))
    )
    (comp (ref "R20")
      (value "4K7")
      (footprint "eagle-import:R0805")
      (libsource (lib "eagle-import") (part "R-EU_R0805"))
    )
    (comp (ref "R21")
      (value "4K7")
      (footprint "eagle-import:R0805")
      (libsource (lib "eagle-import") (part "R-EU_R0805"))
    )
    (comp (ref "R22")
      (value "1K")
      (footprint "eagle-import:R0805")
      (libsource (lib "eagle-import") (part "R-EU_R0805"))
    )
    (comp (ref "READY")
      (value "READY")
      (footprint "eagle-import:AK500_3")
      (libsource (lib "eagle-import") (part "AK500/3"))
    )
    (comp (ref "SJ1") (value "SJ") (footprint "eagle-import:SJ") (libsource (lib "eagle-import") (part "SJ")))
  )
  (nets
    (net (code "1") (name "+12V") (class "Default")
      (node (ref "C1") (pin "2") (pinfunction "2_2") (pintype "passive"))
      (node (ref "C2") (pin "1") (pinfunction "1_1") (pintype "passive"))
      (node (ref "C5") (pin "1") (pinfunction "1_1") (pintype "passive"))
      (node (ref "IC6") (pin "4") (pinfunction "V+_4") (pintype "power_in"))
      (node (ref "IC7") (pin "4") (pinfunction "V+_4") (pintype "power_in"))
      (node (ref "IC8") (pin "4") (pinfunction "V+_4") (pintype "power_in"))
      (node (ref "LED3") (pin "A") (pinfunction "A_A") (pintype "passive"))
      (node (ref "OUTPUT") (pin "5") (pinfunction "5_5") (pintype "passive"))
      (node (ref "U1") (pin "3") (pinfunction "+VOUT_3") (pintype "passive"))
    )
    (net (code "2") (name "-12V") (class "Default")
      (node (ref "C5") (pin "2") (pinfunction "2_2") (pintype "passive"))
      (node (ref "C6") (pin "2") (pinfunction "2_2") (pintype "passive"))
      (node (ref "C7") (pin "1") (pinfunction "1_1") (pintype "passive"))
      (node (ref "IC6") (pin "11") (pinfunction "V-_11") (pintype "power_in"))
      (node (ref "IC7") (pin "11") (pinfunction "V-_11") (pintype "power_in"))
      (node (ref "IC8") (pin "11") (pinfunction "V-_11") (pintype "power_in"))
      (node (ref "LED5") (pin "C") (pinfunction "C_C") (pintype "passive"))
      (node (ref "OUTPUT") (pin "4") (pinfunction "4_4") (pintype "passive"))
      (node (ref "U1") (pin "5") (pinfunction "-VOUT_5") (pintype "passive"))
    )
    (net (code "3") (name "3V3") (class "Default")
      (node (ref "C14") (pin "1") (pinfunction "1_1") (pintype "passive"))
      (node (ref "C42") (pin "2") (pinfunction "2_2") (pintype "passive"))
      (node (ref "C46") (pin "2") (pinfunction "2_2") (pintype "passive"))
      (node (ref "C47") (pin "2") (pinfunction "2_2") (pintype "passive"))
      (node (ref "C48") (pin "1") (pinfunction "1_1") (pintype "passive"))
      (node (ref "C49") (pin "2") (pinfunction "2_2") (pintype "passive"))
      (node (ref "C50") (pin "1") (pinfunction "1_1") (pintype "passive"))
      (node (ref "C55") (pin "+") (pinfunction "+_+") (pintype "passive"))
      (node (ref "D4") (pin "C") (pinfunction "C_C") (pintype "passive"))
      (node (ref "IC1") (pin "8") (pinfunction "OUT_8") (pintype "output"))
      (node (ref "IC10") (pin "8") (pinfunction "VCC_8") (pintype "power_in"))
      (node (ref "IC11") (pin "10") (pinfunction "VDD_10") (pintype "power_in"))
      (node (ref "IC11") (pin "19") (pinfunction "AVDD_19") (pintype "power_in"))
      (node (ref "IC11") (pin "26") (pinfunction "VDD_26") (pintype "power_in"))
      (node (ref "IC11") (pin "35") (pinfunction "VUSB3V3_35") (pintype "bidirectional"))
      (node (ref "IC11") (pin "38") (pinfunction "VDD_38") (pintype "power_in"))
      (node (ref "IC11") (pin "57") (pinfunction "VDD_57") (pintype "passive"))
      (node (ref "IC13") (pin "14") (pinfunction "VCC_14") (pintype "power_in"))
      (node (ref "IC3") (pin "3") (pinfunction "V+_3") (pintype "power_in"))
      (node (ref "IC4") (pin "3") (pinfunction "V+_3") (pintype "power_in"))
      (node (ref "IC5") (pin "3") (pinfunction "V+_3") (pintype "power_in"))
      (node (ref "ICSP") (pin "2") (pinfunction "2_2") (pintype "passive"))
      (node (ref "LED8") (pin "A") (pinfunction "A_A") (pintype "passive"))
      (node (ref "OK2") (pin "8") (pinfunction "VCC_8") (pintype "power_in"))
      (node (ref "OK3") (pin "8") (pinfunction "VCC_8") (pintype "power_in"))
      (node (ref "OK4") (pin "8") (pinfunction "VCC_8") (pintype "power_in"))
      (node (ref "R14") (pin "2") (pinfunction "2_2") (pintype "passive"))
      (node (ref "R16") (pin "2") (pinfunction "2_2") (pintype "passive"))
      (node (ref "R18") (pin "2") (pinfunction "2_2") (pintype "passive"))
      (node (ref "R21") (pin "2") (pinfunction "2_2") (pintype "passive"))
      (node (ref "R23") (pin "2") (pinfunction "2_2") (pintype "passive"))
      (node (ref "R24") (pin "2") (pinfunction "2_2") (pintype "passive"))
      (node (ref "R27") (pin "2") (pinfunction "2_2") (pintype "passive"))
      (node (ref "R28") (pin "2") (pinfunction "2_2") (pintype "passive"))
      (node (ref "R31") (pin "2") (pinfunction "2_2") (pintype "passive"))
      (node (ref "R33") (pin "2") (pinfunction "2_2") (pintype "passive"))
      (node (ref "R35") (pin "2") (pinfunction "2_2") (pintype "passive"))
      (node (ref "R36") (pin "2") (pinfunction "2_2") (pintype "passive"))
      (node (ref "R37") (pin "2") (pinfunction "2_2") (pintype "passive"))
      (node (ref "R38") (pin "2") (pinfunction "2_2") (pintype "passive"))
      (node (ref "R39") (pin "2") (pinfunction "2_2") (pintype "passive"))
      (node (ref "R40") (pin "2") (pinfunction "2_2") (pintype "passive"))
      (node (ref "R41") (pin "2") (pinfunction "2_2") (pintype "passive"))
      (node (ref "R42") (pin "2") (pinfunction "2_2") (pintype "passive"))
      (node (ref "R43") (pin "2") (pinfunction "2_2") (pintype "passive"))
      (node (ref "R86") (pin "1") (pinfunction "1_1") (pintype "passive"))
      (node (ref "R87") (pin "1") (pinfunction "1_1") (pintype "passive"))
      (node (ref "R91") (pin "2") (pinfunction "2_2") (pintype "passive"))
      (node (ref "R95") (pin "1") (pinfunction "1_1") (pintype "passive"))
      (node (ref "R96") (pin "1") (pinfunction "1_1") (pintype "passive"))
      (node (ref "S1") (pin "1") (pinfunction "1_1") (pintype "passive"))
      (node (ref "S1") (pin "2") (pinfunction "2_2") (pintype "passive"))
      (node (ref "S1") (pin "3") (pinfunction "3_3") (pintype "passive"))
      (node (ref "S1") (pin "4") (pinfunction "4_4") (pintype "passive"))
    )
    (net (code "4") (name "5V") (class "Default")
      (node (ref "C11") (pin "1") (pinfunction "1_1") (pintype "passive"))
      (node (ref "C13") (pin "+") (pinfunction "+_+") (pintype "passive"))
      (node (ref "C19") (pin "2") (pinfunction "2_2") (pintype "passive"))
      (node (ref "C20") (pin "2") (pinfunction "2_2") (pintype "passive"))
      (node (ref "C21") (pin "2") (pinfunction "2_2") (pintype "passive"))
      (node (ref "C8") (pin "2") (pinfunction "2_2") (pintype "passive"))
      (node (ref "D1") (pin "2") (pinfunction "C_2") (pintype "passive"))
      (node (ref "ENCODER1") (pin "2") (pinfunction "2_2") (pintype "passive"))
      (node (ref "ENCODER1") (pin "6") (pinfunction "6_6") (pintype "passive"))
      (node (ref "ENCODER2") (pin "2") (pinfunction "2_2") (pintype "passive"))
      (node (ref "ENCODER2") (pin "6") (pinfunction "6_6") (pintype "passive"))
      (node (ref "ENCODER3") (pin "2") (pinfunction "2_2") (pintype "passive"))
      (node (ref "ENCODER3") (pin "6") (pinfunction "6_6") (pintype "passive"))
      (node (ref "IC1") (pin "1") (pinfunction "+IN_1") (pintype "power_in"))
      (node (ref "IC1") (pin "4") (pinfunction "~{OFF}_4") (pintype "input"))
      (node (ref "INTERFACE") (pin "14") (pinfunction "14_14") (pintype "passive"))
      (node (ref "K1") (pin "1") (pinfunction "+_1") (pintype "passive"))
      (node (ref "LED6") (pin "A") (pinfunction "A_A") (pintype "passive"))
      (node (ref "R44") (pin "2") (pinfunction "2_2") (pintype "passive"))
      (node (ref "U2") (pin "4") (pinfunction "+VOUT_4") (pintype "passive"))
    )
    (net (code "5") (name "24VGND") (class "Default")
      (node (ref "C10") (pin "2") (pinfunction "2_2") (pintype "passive"))
      (node (ref "C12") (pin "2") (pinfunction "2_2") (pintype "passive"))
      (node (ref "C3") (pin "-") (pinfunction "-_-") (pintype "passive"))
      (node (ref "C4") (pin "2") (pinfunction "2_2") (pintype "passive"))
      (node (ref "C7") (pin "2") (pinfunction "2_2") (pintype "passive"))
      (node (ref "C9") (pin "-") (pinfunction "-_-") (pintype "passive"))
      (node (ref "LED1") (pin "C") (pinfunction "C_C") (pintype "passive"))
      (node (ref "LED2") (pin "C") (pinfunction "C_C") (pintype "passive"))
      (node (ref "POWER") (pin "2") (pinfunction "KL_2") (pintype "passive"))
      (node (ref "Q3") (pin "2") (pinfunction "E_2") (pintype "passive"))
      (node (ref "Q4") (pin "2") (pinfunction "E_2") (pintype "passive"))
      (node (ref "U1") (pin "2") (pinfunction "-VIN_2") (pintype "passive"))
      (node (ref "U2") (pin "2") (pinfunction "-VIN_2") (pintype "passive"))
    )
    (net (code "6") (name "24V_1") (class "Default")
      (node (ref "C3") (pin "+") (pinfunction "+_+") (pintype "passive"))
      (node (ref "C4") (pin "1") (pinfunction "1_1") (pintype "passive"))
      (node (ref "D2") (pin "1") (pinfunction "A_1") (pintype "passive"))
      (node (ref "F1") (pin "2") (pinfunction "2_2") (pintype "passive"))
      (node (ref "L1") (pin "A") (pinfunction "1_A") (pintype "passive"))
    )
    (net (code "7") (name "24V_2") (class "Default")
      (node (ref "C10") (pin "1") (pinfunction "1_1") (pintype "passive"))
      (node (ref "C9") (pin "+") (pinfunction "+_+") (pintype "passive"))
      (node (ref "D3") (pin "1") (pinfunction "A_1") (pintype "passive"))
      (node (ref "F2") (pin "2") (pinfunction "2_2") (pintype "passive"))
      (node (ref "L2") (pin "A") (pinfunction "1_A") (pintype "passive"))
    )
    (net (code "8") (name "CH1_A+") (class "Default")
      (node (ref "ENCODER1") (pin "3") (pinfunction "3_3") (pintype "passive"))
      (node (ref "IC3") (pin "7") (pinfunction "+IN_7") (pintype "input"))
    )
    (net (code "9") (name "CH1_A-") (class "Default")
      (node (ref "ENCODER1") (pin "7") (pinfunction "7_7") (pintype "passive"))
      (node (ref "IC3") (pin "6") (pinfunction "-IN_6") (pintype "input"))
      (node (ref "SJ2") (pin "2") (pinfunction "2_2") (pintype "passive"))
    )
    (net (code "10") (name "CH1_B+") (class "Default")
      (node (ref "ENCODER1") (pin "4") (pinfunction "4_4") (pintype "passive"))
      (node (ref "IC3") (pin "5") (pinfunction "+IN_5") (pintype "input"))
    )
    (net (code "11") (name "CH1_B-") (class "Default")
      (node (ref "ENCODER1") (pin "8") (pinfunction "8_8") (pintype "passive"))
      (node (ref "IC3") (pin "4") (pinfunction "-IN_4") (pintype "input"))
      (node (ref "SJ5") (pin "2") (pinfunction "2_2") (pintype "passive"))
    )
    (net (code "12") (name "CH1_CMD") (class "Default")
      (node (ref "IC6") (pin "13") (pinfunction "-IN_13") (pintype "input"))
      (node (ref "IC6") (pin "14") (pinfunction "OUT_14") (pintype "output"))
      (node (ref "OUTPUT") (pin "1") (pinfunction "1_1") (pintype "passive"))
    )
    (net (code "13") (name "CH1_DIR") (class "Default")
      (node (ref "IC11") (pin "21") (pinfunction "OA3OUT/AN6/CVD6/C3IN4-/C4IN1+/C4IN4-/RPC0/RC0_21") (pintype "bidirectional"))
      (node (ref "OK2") (pin "6") (pinfunction "VO_6") (pintype "passive"))
      (node (ref "R27") (pin "1") (pinfunction "1_1") (pintype "passive"))
    )
    (net (code "14") (name "CH1_DIR_H") (class "Default")
      (node (ref "INTERFACE") (pin "4") (pinfunction "4_4") (pintype "passive"))
      (node (ref "R29") (pin "1") (pinfunction "1_1") (pintype "passive"))
    )
    (net (code "15") (name "CH1_DIR_L") (class "Default")
      (node (ref "INTERFACE") (pin "5") (pinfunction "5_5") (pintype "passive"))
      (node (ref "OK2") (pin "3") (pinfunction "C_3") (pintype "passive"))
    )
    (net (code "16") (name "CH1_H") (class "Default")
      (node (ref "IC11") (pin "2") (pinfunction "RPB14/PWM1H/VBUSON1/PMPD6/RB14_2") (pintype "bidirectional"))
      (node (ref "R48") (pin "1") (pinfunction "1_1") (pintype "passive"))
    )
    (net (code "17") (name "CH1_I+") (class "Default")
      (node (ref "ENCODER1") (pin "5") (pinfunction "5_5") (pintype "passive"))
      (node (ref "IC3") (pin "9") (pinfunction "+IN_9") (pintype "input"))
    )
    (net (code "18") (name "CH1_I-") (class "Default")
      (node (ref "ENCODER1") (pin "9") (pinfunction "9_9") (pintype "passive"))
      (node (ref "IC3") (pin "8") (pinfunction "-IN_8") (pintype "input"))
      (node (ref "SJ8") (pin "2") (pinfunction "2_2") (pintype "passive"))
    )
    (net (code "19") (name "CH1_L") (class "Default")
      (node (ref "IC11") (pin "3") (pinfunction "RPB15/PWM7H/PWM1L/PMPD7/RB15_3") (pintype "bidirectional"))
      (node (ref "R55") (pin "1") (pinfunction "1_1") (pintype "passive"))
    )
    (net (code "20") (name "CH1_QE_A") (class "Default")
      (node (ref "IC11") (pin "30") (pinfunction "AN15/CVD15/RPE15/FLT8/PMPA0/PSPA0/RE15_30") (pintype "bidirectional"))
      (node (ref "IC3") (pin "1") (pinfunction "OUT_1") (pintype "open_collector"))
      (node (ref "R38") (pin "1") (pinfunction "1_1") (pintype "passive"))
    )
    (net (code "21") (name "CH1_QE_B") (class "Default")
      (node (ref "IC11") (pin "33") (pinfunction "OA5IN+/DAC1/AN24/CVD24/C5IN1+/C5IN3-/RPA4/T1CK/T1G/RA4_33") (pintype "bidirectional"))
      (node (ref "IC3") (pin "2") (pinfunction "OUT_2") (pintype "open_collector"))
      (node (ref "R35") (pin "1") (pinfunction "1_1") (pintype "passive"))
    )
    (net (code "22") (name "CH1_QE_I") (class "Default")
      (node (ref "IC11") (pin "31") (pinfunction "TDI/DAC3/AN26/CVD26/RPA8/PMPA9/RA8_31") (pintype "bidirectional"))
      (node (ref "IC3") (pin "14") (pinfunction "OUT_14") (pintype "open_collector"))
      (node (ref "R41") (pin "1") (pinfunction "1_1") (pintype "passive"))
    )
    (net (code "23") (name "CH1_STEP") (class "Default")
      (node (ref "IC11") (pin "18") (pinfunction "PGED1/OA1IN-/AN5/CTCMP/C1IN1-/RTCC/RPB3/RB3_18") (pintype "bidirectional"))
      (node (ref "OK2") (pin "7") (pinfunction "VO_7") (pintype "passive"))
      (node (ref "R23") (pin "1") (pinfunction "1_1") (pintype "passive"))
    )
    (net (code "24") (name "CH1_STEP_H") (class "Default")
      (node (ref "INTERFACE") (pin "2") (pinfunction "2_2") (pintype "passive"))
      (node (ref "R25") (pin "1") (pinfunction "1_1") (pintype "passive"))
    )
    (net (code "25") (name "CH1_STEP_L") (class "Default")
      (node (ref "INTERFACE") (pin "3") (pinfunction "3_3") (pintype "passive"))
      (node (ref "OK2") (pin "2") (pinfunction "C_2") (pintype "passive"))
    )
    (net (code "26") (name "CH2_A+") (class "Default")
      (node (ref "ENCODER2") (pin "3") (pinfunction "3_3") (pintype "passive"))
      (node (ref "IC4") (pin "5") (pinfunction "+IN_5") (pintype "input"))
    )
    (net (code "27") (name "CH2_A-") (class "Default")
      (node (ref "ENCODER2") (pin "7") (pinfunction "7_7") (pintype "passive"))
      (node (ref "IC4") (pin "4") (pinfunction "-IN_4") (pintype "input"))
      (node (ref "SJ3") (pin "2") (pinfunction "2_2") (pintype "passive"))
    )
    (net (code "28") (name "CH2_B+") (class "Default")
      (node (ref "ENCODER2") (pin "4") (pinfunction "4_4") (pintype "passive"))
      (node (ref "IC4") (pin "7") (pinfunction "+IN_7") (pintype "input"))
    )
    (net (code "29") (name "CH2_B-") (class "Default")
      (node (ref "ENCODER2") (pin "8") (pinfunction "8_8") (pintype "passive"))
      (node (ref "IC4") (pin "6") (pinfunction "-IN_6") (pintype "input"))
      (node (ref "SJ6") (pin "2") (pinfunction "2_2") (pintype "passive"))
    )
    (net (code "30") (name "CH2_CMD") (class "Default")
      (node (ref "IC7") (pin "13") (pinfunction "-IN_13") (pintype "input"))
      (node (ref "IC7") (pin "14") (pinfunction "OUT_14") (pintype "output"))
      (node (ref "OUTPUT") (pin "2") (pinfunction "2_2") (pintype "passive"))
    )
    (net (code "31") (name "CH2_DIR") (class "Default")
      (node (ref "IC11") (pin "32") (pinfunction "FLT15/RPB4/PMPA8/RB4_32") (pintype "bidirectional"))
      (node (ref "OK3") (pin "6") (pinfunction "VO_6") (pintype "passive"))
      (node (ref "R28") (pin "1") (pinfunction "1_1") (pintype "passive"))
    )
    (net (code "32") (name "CH2_DIR_H") (class "Default")
      (node (ref "INTERFACE") (pin "8") (pinfunction "8_8") (pintype "passive"))
      (node (ref "R30") (pin "1") (pinfunction "1_1") (pintype "passive"))
    )
    (net (code "33") (name "CH2_DIR_L") (class "Default")
      (node (ref "INTERFACE") (pin "9") (pinfunction "9_9") (pintype "passive"))
      (node (ref "OK3") (pin "3") (pinfunction "C_3") (pintype "passive"))
    )
    (net (code "34") (name "CH2_H") (class "Default")
      (node (ref "IC11") (pin "64") (pinfunction "TDO/PWM4H/PMPD4/RA10_64") (pintype "bidirectional"))
      (node (ref "R61") (pin "1") (pinfunction "1_1") (pintype "passive"))
    )
    (net (code "35") (name "CH2_I+") (class "Default")
      (node (ref "ENCODER2") (pin "5") (pinfunction "5_5") (pintype "passive"))
      (node (ref "IC4") (pin "9") (pinfunction "+IN_9") (pintype "input"))
    )
    (net (code "36") (name "CH2_I-") (class "Default")
      (node (ref "ENCODER2") (pin "9") (pinfunction "9_9") (pintype "passive"))
      (node (ref "IC4") (pin "8") (pinfunction "-IN_8") (pintype "input"))
      (node (ref "SJ9") (pin "2") (pinfunction "2_2") (pintype "passive"))
    )
    (net (code "37") (name "CH2_L") (class "Default")
      (node (ref "IC11") (pin "1") (pinfunction "TCK/RPA7/PWM10H/PWM4L/PMPD5/RA7_1") (pintype "bidirectional"))
      (node (ref "R68") (pin "1") (pinfunction "1_1") (pintype "passive"))
    )
    (net (code "38") (name "CH2_QE_A") (class "Default")
      (node (ref "IC11") (pin "23") (pinfunction "OA3IN+/AN8/CVD8/C3IN1+/C3IN3-/RPC2/FLT3/PMPA13/RC2_23") (pintype "input"))
      (node (ref "IC4") (pin "2") (pinfunction "OUT_2") (pintype "open_collector"))
      (node (ref "R36") (pin "1") (pinfunction "1_1") (pintype "passive"))
    )
    (net (code "39") (name "CH2_QE_B") (class "Default")
      (node (ref "IC11") (pin "22") (pinfunction "OA3IN-/AN7/CVD7/C3IN1-/C4IN1-/RPC1/PMPA7/RC1_22") (pintype "bidirectional"))
      (node (ref "IC4") (pin "1") (pinfunction "OUT_1") (pintype "open_collector"))
      (node (ref "R39") (pin "1") (pinfunction "1_1") (pintype "passive"))
    )
    (net (code "40") (name "CH2_QE_I") (class "Default")
      (node (ref "IC11") (pin "16") (pinfunction "PGEC3/OA1OUT/VREF+/AN3/C1IN4-/C4IN2-/RPB1/CTED1/PMPA6/RB1_16") (pintype "bidirectional"))
      (node (ref "IC4") (pin "14") (pinfunction "OUT_14") (pintype "open_collector"))
      (node (ref "R42") (pin "1") (pinfunction "1_1") (pintype "passive"))
    )
    (net (code "41") (name "CH2_STEP") (class "Default")
      (node (ref "IC11") (pin "29") (pinfunction "AN14/CVD14/RPE14/FLT7/PMPA1/PSPA1/RE14_29") (pintype "bidirectional"))
      (node (ref "OK3") (pin "7") (pinfunction "VO_7") (pintype "passive"))
      (node (ref "R24") (pin "1") (pinfunction "1_1") (pintype "passive"))
    )
    (net (code "42") (name "CH2_STEP_H") (class "Default")
      (node (ref "INTERFACE") (pin "6") (pinfunction "6_6") (pintype "passive"))
      (node (ref "R26") (pin "1") (pinfunction "1_1") (pintype "passive"))
    )
    (net (code "43") (name "CH2_STEP_L") (class "Default")
      (node (ref "INTERFACE") (pin "7") (pinfunction "7_7") (pintype "passive"))
      (node (ref "OK3") (pin "2") (pinfunction "C_2") (pintype "passive"))
    )
    (net (code "44") (name "CH3_A+") (class "Default")
      (node (ref "ENCODER3") (pin "3") (pinfunction "3_3") (pintype "passive"))
      (node (ref "IC5") (pin "5") (pinfunction "+IN_5") (pintype "input"))
    )
    (net (code "45") (name "CH3_A-") (class "Default")
      (node (ref "ENCODER3") (pin "7") (pinfunction "7_7") (pintype "passive"))
      (node (ref "IC5") (pin "4") (pinfunction "-IN_4") (pintype "input"))
      (node (ref "SJ4") (pin "2") (pinfunction "2_2") (pintype "passive"))
    )
    (net (code "46") (name "CH3_B+") (class "Default")
      (node (ref "ENCODER3") (pin "4") (pinfunction "4_4") (pintype "passive"))
      (node (ref "IC5") (pin "7") (pinfunction "+IN_7") (pintype "input"))
    )
    (net (code "47") (name "CH3_B-") (class "Default")
      (node (ref "ENCODER3") (pin "8") (pinfunction "8_8") (pintype "passive"))
      (node (ref "IC5") (pin "6") (pinfunction "-IN_6") (pintype "input"))
      (node (ref "SJ7") (pin "2") (pinfunction "2_2") (pintype "passive"))
    )
    (net (code "48") (name "CH3_CMD") (class "Default")
      (node (ref "IC8") (pin "13") (pinfunction "-IN_13") (pintype "input"))
      (node (ref "IC8") (pin "14") (pinfunction "OUT_14") (pintype "output"))
      (node (ref "OUTPUT") (pin "3") (pinfunction "3_3") (pintype "passive"))
    )
    (net (code "49") (name "CH3_DIR") (class "Default")
      (node (ref "IC11") (pin "24") (pinfunction "AN11/CVD11/C1IN2-/FLT4/PMPA12/RC11_24") (pintype "output"))
      (node (ref "OK4") (pin "6") (pinfunction "VO_6") (pintype "passive"))
      (node (ref "R33") (pin "1") (pinfunction "1_1") (pintype "passive"))
    )
    (net (code "50") (name "CH3_DIR_H") (class "Default")
      (node (ref "INTERFACE") (pin "12") (pinfunction "12_12") (pintype "passive"))
      (node (ref "R34") (pin "1") (pinfunction "1_1") (pintype "passive"))
    )
    (net (code "51") (name "CH3_DIR_L") (class "Default")
      (node (ref "INTERFACE") (pin "13") (pinfunction "13_13") (pintype "passive"))
      (node (ref "OK4") (pin "3") (pinfunction "C_3") (pintype "passive"))
    )
    (net (code "52") (name "CH3_H") (class "Default")
      (node (ref "IC11") (pin "62") (pinfunction "RPB12/PWM2H/PMPD2/RB12_62") (pintype "bidirectional"))
      (node (ref "R74") (pin "1") (pinfunction "1_1") (pintype "passive"))
    )
    (net (code "53") (name "CH3_I+") (class "Default")
      (node (ref "ENCODER3") (pin "5") (pinfunction "5_5") (pintype "passive"))
      (node (ref "IC5") (pin "9") (pinfunction "+IN_9") (pintype "input"))
    )
    (net (code "54") (name "CH3_I-") (class "Default")
      (node (ref "ENCODER3") (pin "9") (pinfunction "9_9") (pintype "passive"))
      (node (ref "IC5") (pin "8") (pinfunction "-IN_8") (pintype "input"))
      (node (ref "SJ10") (pin "2") (pinfunction "2_2") (pintype "passive"))
    )
    (net (code "55") (name "CH3_L") (class "Default")
      (node (ref "IC11") (pin "63") (pinfunction "RPB13/PWM8H/PWM2L/CTPLS/PMPD3/RB13_63") (pintype "bidirectional"))
      (node (ref "R81") (pin "1") (pinfunction "1_1") (pintype "passive"))
    )
    (net (code "56") (name "CH3_QE_A") (class "Default")
      (node (ref "IC11") (pin "13") (pinfunction "OA2OUT/ANO/C2IN4-/C4IN3-/RPA0/RA0_13") (pintype "bidirectional"))
      (node (ref "IC5") (pin "2") (pinfunction "OUT_2") (pintype "open_collector"))
      (node (ref "R37") (pin "1") (pinfunction "1_1") (pintype "passive"))
    )
    (net (code "57") (name "CH3_QE_B") (class "Default")
      (node (ref "IC11") (pin "14") (pinfunction "OA2IN+/AN1/C2IN1+/RPA1/RA1_14") (pintype "bidirectional"))
      (node (ref "IC5") (pin "1") (pinfunction "OUT_1") (pintype "open_collector"))
      (node (ref "R40") (pin "1") (pinfunction "1_1") (pintype "passive"))
    )
    (net (code "58") (name "CH3_QE_I") (class "Default")
      (node (ref "IC11") (pin "17") (pinfunction "PGEC1/OA1IN+/AN4/C1IN1+/C1IN3-/C2IN3-/RPB2/RB2_17") (pintype "bidirectional"))
      (node (ref "IC5") (pin "14") (pinfunction "OUT_14") (pintype "open_collector"))
      (node (ref "R43") (pin "1") (pinfunction "1_1") (pintype "passive"))
    )
    (net (code "59") (name "CH3_STEP") (class "Default")
      (node (ref "IC11") (pin "15") (pinfunction "PGED3/VREF-/OA2IN-/AN2/C2IN1-/RPB0/CTED2/RB0_15") (pintype "bidirectional"))
      (node (ref "OK4") (pin "7") (pinfunction "VO_7") (pintype "passive"))
      (node (ref "R31") (pin "1") (pinfunction "1_1") (pintype "passive"))
    )
    (net (code "60") (name "CH3_STEP_H") (class "Default")
      (node (ref "INTERFACE") (pin "10") (pinfunction "10_10") (pintype "passive"))
      (node (ref "R32") (pin "1") (pinfunction "1_1") (pintype "passive"))
    )
    (net (code "61") (name "CH3_STEP_L") (class "Default")
      (node (ref "INTERFACE") (pin "11") (pinfunction "11_11") (pintype "passive"))
      (node (ref "OK4") (pin "2") (pinfunction "C_2") (pintype "passive"))
    )
    (net (code "62") (name "DI1") (class "Default")
      (node (ref "IC11") (pin "4") (pinfunction "AN19/CVD19/RPG6/PMPA5/RG6_4") (pintype "bidirectional"))
      (node (ref "OK1") (pin "16") (pinfunction "C_16") (pintype "passive"))
      (node (ref "R14") (pin "1") (pinfunction "1_1") (pintype "passive"))
    )
    (net (code "63") (name "DI1_CON") (class "Default")
      (node (ref "INTERFACE") (pin "16") (pinfunction "16_16") (pintype "passive"))
      (node (ref "R15") (pin "1") (pinfunction "1_1") (pintype "passive"))
    )
    (net (code "64") (name "DI2") (class "Default")
      (node (ref "IC11") (pin "5") (pinfunction "AN18/CVD18/RPG7/PMPA4/RG7_5") (pintype "bidirectional"))
      (node (ref "OK1") (pin "14") (pinfunction "C_14") (pintype "passive"))
      (node (ref "R16") (pin "1") (pinfunction "1_1") (pintype "passive"))
    )
    (net (code "65") (name "DI2_CON") (class "Default")
      (node (ref "INTERFACE") (pin "17") (pinfunction "17_17") (pintype "passive"))
      (node (ref "R17") (pin "1") (pinfunction "1_1") (pintype "passive"))
    )
    (net (code "66") (name "DI3") (class "Default")
      (node (ref "IC11") (pin "6") (pinfunction "AN17/CVD17/RPG8/PMPA3/RG8_6") (pintype "bidirectional"))
      (node (ref "OK1") (pin "12") (pinfunction "C_12") (pintype "passive"))
      (node (ref "R18") (pin "1") (pinfunction "1_1") (pintype "passive"))
    )
    (net (code "67") (name "DI3_CON") (class "Default")
      (node (ref "INTERFACE") (pin "18") (pinfunction "18_18") (pintype "passive"))
      (node (ref "R19") (pin "1") (pinfunction "1_1") (pintype "passive"))
    )
    (net (code "68") (name "DI4") (class "Default")
      (node (ref "IC11") (pin "8") (pinfunction "AN16/CVD16/RPG9/PMPA2/RG9_8") (pintype "bidirectional"))
      (node (ref "OK1") (pin "10") (pinfunction "C_10") (pintype "passive"))
      (node (ref "R21") (pin "1") (pinfunction "1_1") (pintype "passive"))
    )
    (net (code "69") (name "DI4_CON") (class "Default")
      (node (ref "INTERFACE") (pin "19") (pinfunction "19_19") (pintype "passive"))
      (node (ref "R22") (pin "1") (pinfunction "1_1") (pintype "passive"))
    )
    (net (code "70") (name "DI_COM_CON") (class "Default")
      (node (ref "C15") (pin "2") (pinfunction "2_2") (pintype "passive"))
      (node (ref "C16") (pin "2") (pinfunction "2_2") (pintype "passive"))
      (node (ref "C17") (pin "2") (pinfunction "2_2") (pintype "passive"))
      (node (ref "C18") (pin "2") (pinfunction "2_2") (pintype "passive"))
      (node (ref "INTERFACE") (pin "20") (pinfunction "20_20") (pintype "passive"))
      (node (ref "OK1") (pin "2") (pinfunction "AC2_2") (pintype "passive"))
      (node (ref "OK1") (pin "4") (pinfunction "AC2_4") (pintype "passive"))
      (node (ref "OK1") (pin "6") (pinfunction "AC2_6") (pintype "passive"))
      (node (ref "OK1") (pin "8") (pinfunction "AC2_8") (pintype "passive"))
    )
    (net (code "71") (name "DO1") (class "Default")
      (node (ref "IC11") (pin "52") (pinfunction "TRD1/RPC8/PWM5H/PMPWR/PSPWR/RC8_52") (pintype "bidirectional"))
      (node (ref "IC2") (pin "14") (pinfunction "I4_14") (pintype "input"))
    )
    (net (code "72") (name "DO1_CON") (class "Default")
      (node (ref "IC2") (pin "16") (pinfunction "C4_16") (pintype "open_collector"))
      (node (ref "INTERFACE") (pin "21") (pinfunction "21_21") (pintype "passive"))
    )
    (net (code "73") (name "DO2") (class "Default")
      (node (ref "IC11") (pin "53") (pinfunction "TRD2/RPD5/PWM12H/PMPRD/PSPRD/RD5_53") (pintype "bidirectional"))
      (node (ref "IC2") (pin "11") (pinfunction "I3_11") (pintype "input"))
    )
    (net (code "74") (name "DO2_CON") (class "Default")
      (node (ref "IC2") (pin "9") (pinfunction "C3_9") (pintype "open_collector"))
      (node (ref "INTERFACE") (pin "22") (pinfunction "22_22") (pintype "passive"))
    )
    (net (code "75") (name "DO3") (class "Default")
      (node (ref "IC11") (pin "11") (pinfunction "AN10/CVD10/RPA12/RA12_11") (pintype "bidirectional"))
      (node (ref "IC2") (pin "3") (pinfunction "I1_3") (pintype "input"))
    )
    (net (code "76") (name "DO3_CON") (class "Default")
      (node (ref "IC2") (pin "1") (pinfunction "C1_1") (pintype "open_collector"))
      (node (ref "INTERFACE") (pin "23") (pinfunction "23_23") (pintype "passive"))
    )
    (net (code "77") (name "DO4") (class "Default")
      (node (ref "IC11") (pin "12") (pinfunction "AN9/CVD9/RPA11/USBOEN1/RA11_12") (pintype "bidirectional"))
      (node (ref "IC2") (pin "6") (pinfunction "I2_6") (pintype "input"))
    )
    (net (code "78") (name "DO4_CON") (class "Default")
      (node (ref "IC2") (pin "8") (pinfunction "C2_8") (pintype "open_collector"))
      (node (ref "INTERFACE") (pin "24") (pinfunction "24_24") (pintype "passive"))
    )
    (net (code "79") (name "DO_COM_CON") (class "Default")
      (node (ref "IC2") (pin "10") (pinfunction "E3_10") (pintype "open_collector"))
      (node (ref "IC2") (pin "15") (pinfunction "E4_15") (pintype "open_collector"))
      (node (ref "IC2") (pin "2") (pinfunction "E1_2") (pintype "open_collector"))
      (node (ref "IC2") (pin "7") (pinfunction "E2_7") (pintype "open_collector"))
      (node (ref "INTERFACE") (pin "25") (pinfunction "25_25") (pintype "passive"))
      (node (ref "SJ1") (pin "2") (pinfunction "2_2") (pintype "passive"))
    )
    (net (code "80") (name "GND") (class "Default")
      (node (ref "C11") (pin "2") (pinfunction "2_2") (pintype "passive"))
      (node (ref "C12") (pin "1") (pinfunction "1_1") (pintype "passive"))
      (node (ref "C13") (pin "-") (pinfunction "-_-") (pintype "passive"))
      (node (ref "C14") (pin "2") (pinfunction "2_2") (pintype "passive"))
      (node (ref "C19") (pin "1") (pinfunction "1_1") (pintype "passive"))
      (node (ref "C2") (pin "2") (pinfunction "2_2") (pintype "passive"))
      (node (ref "C20") (pin "1") (pinfunction "1_1") (pintype "passive"))
      (node (ref "C21") (pin "1") (pinfunction "1_1") (pintype "passive"))
      (node (ref "C22") (pin "1") (pinfunction "1_1") (pintype "passive"))
      (node (ref "C24") (pin "2") (pinfunction "2_2") (pintype "passive"))
      (node (ref "C26") (pin "2") (pinfunction "2_2") (pintype "passive"))
      (node (ref "C27") (pin "1") (pinfunction "1_1") (pintype "passive"))
      (node (ref "C29") (pin "2") (pinfunction "2_2") (pintype "passive"))
      (node (ref "C31") (pin "2") (pinfunction "2_2") (pintype "passive"))
      (node (ref "C32") (pin "1") (pinfunction "1_1") (pintype "passive"))
      (node (ref "C34") (pin "2") (pinfunction "2_2") (pintype "passive"))
      (node (ref "C36") (pin "2") (pinfunction "2_2") (pintype "passive"))
      (node (ref "C42") (pin "1") (pinfunction "1_1") (pintype "passive"))
      (node (ref "C43") (pin "1") (pinfunction "1_1") (pintype "passive"))
      (node (ref "C44") (pin "1") (pinfunction "1_1") (pintype "passive"))
      (node (ref "C45") (pin "1") (pinfunction "1_1") (pintype "passive"))
      (node (ref "C46") (pin "1") (pinfunction "1_1") (pintype "passive"))
      (node (ref "C47") (pin "1") (pinfunction "1_1") (pintype "passive"))
      (node (ref "C48") (pin "2") (pinfunction "2_2") (pintype "passive"))
      (node (ref "C49") (pin "1") (pinfunction "1_1") (pintype "passive"))
      (node (ref "C50") (pin "2") (pinfunction "2_2") (pintype "passive"))
      (node (ref "C55") (pin "-") (pinfunction "-_-") (pintype "passive"))
      (node (ref "C6") (pin "1") (pinfunction "1_1") (pintype "passive"))
      (node (ref "D4") (pin "A") (pinfunction "A_A") (pintype "passive"))
      (node (ref "ENCODER1") (pin "1") (pinfunction "1_1") (pintype "passive"))
      (node (ref "ENCODER1") (pin "G1") (pinfunction "G1_G1") (pintype "passive"))
      (node (ref "ENCODER1") (pin "G2") (pinfunction "G2_G2") (pintype "passive"))
      (node (ref "ENCODER2") (pin "1") (pinfunction "1_1") (pintype "passive"))
      (node (ref "ENCODER2") (pin "G1") (pinfunction "G1_G1") (pintype "passive"))
      (node (ref "ENCODER2") (pin "G2") (pinfunction "G2_G2") (pintype "passive"))
      (node (ref "ENCODER3") (pin "1") (pinfunction "1_1") (pintype "passive"))
      (node (ref "ENCODER3") (pin "G1") (pinfunction "G1_G1") (pintype "passive"))
      (node (ref "ENCODER3") (pin "G2") (pinfunction "G2_G2") (pintype "passive"))
      (node (ref "IC1") (pin "2") (pinfunction "GND_2") (pintype "power_in"))
      (node (ref "IC1") (pin "3") (pinfunction "GND_3") (pintype "power_in"))
      (node (ref "IC1") (pin "5") (pinfunction "SET_5") (pintype "input"))
      (node (ref "IC1") (pin "6") (pinfunction "GND_6") (pintype "power_in"))
      (node (ref "IC1") (pin "7") (pinfunction "GND_7") (pintype "power_in"))
      (node (ref "IC10") (pin "4") (pinfunction "VSS_4") (pintype "power_in"))
      (node (ref "IC11") (pin "20") (pinfunction "AVSS_20") (pintype "power_in"))
      (node (ref "IC11") (pin "25") (pinfunction "VSS_25") (pintype "power_in"))
      (node (ref "IC11") (pin "41") (pinfunction "VSS_41") (pintype "power_in"))
      (node (ref "IC11") (pin "56") (pinfunction "VSS_56") (pintype "power_in"))
      (node (ref "IC11") (pin "9") (pinfunction "VSS_9") (pintype "power_in"))
      (node (ref "IC11") (pin "EXP") (pinfunction "VSS_EXP") (pintype "power_in"))
      (node (ref "IC13") (pin "7") (pinfunction "GND_7") (pintype "power_in"))
      (node (ref "IC2") (pin "12") (pinfunction "SUB3_12") (pintype "passive"))
      (node (ref "IC2") (pin "13") (pinfunction "SUB4_13") (pintype "passive"))
      (node (ref "IC2") (pin "4") (pinfunction "SUB1_4") (pintype "passive"))
      (node (ref "IC2") (pin "5") (pinfunction "SUB2_5") (pintype "passive"))
      (node (ref "IC3") (pin "12") (pinfunction "GND_12") (pintype "power_in"))
      (node (ref "IC4") (pin "12") (pinfunction "GND_12") (pintype "power_in"))
      (node (ref "IC5") (pin "12") (pinfunction "GND_12") (pintype "power_in"))
      (node (ref "ICSP") (pin "3") (pinfunction "3_3") (pintype "passive"))
      (node (ref "INTERFACE") (pin "1") (pinfunction "1_1") (pintype "passive"))
      (node (ref "INTERFACE") (pin "G1") (pinfunction "G1_G1") (pintype "passive"))
      (node (ref "INTERFACE") (pin "G2") (pinfunction "G2_G2") (pintype "passive"))
      (node (ref "LED14") (pin "C") (pinfunction "C_C") (pintype "passive"))
      (node (ref "LED15") (pin "C") (pinfunction "C_C") (pintype "passive"))
      (node (ref "LED16") (pin "C") (pinfunction "C_C") (pintype "passive"))
      (node (ref "OK1") (pin "11") (pinfunction "E_11") (pintype "passive"))
      (node (ref "OK1") (pin "13") (pinfunction "E_13") (pintype "passive"))
      (node (ref "OK1") (pin "15") (pinfunction "E_15") (pintype "passive"))
      (node (ref "OK1") (pin "9") (pinfunction "E_9") (pintype "passive"))
      (node (ref "OK2") (pin "5") (pinfunction "GND_5") (pintype "power_in"))
      (node (ref "OK3") (pin "5") (pinfunction "GND_5") (pintype "power_in"))
      (node (ref "OK4") (pin "5") (pinfunction "GND_5") (pintype "power_in"))
      (node (ref "OUTPUT") (pin "6") (pinfunction "6_6") (pintype "passive"))
      (node (ref "OUTPUT") (pin "7") (pinfunction "7_7") (pintype "passive"))
      (node (ref "OUTPUT") (pin "8") (pinfunction "8_8") (pintype "passive"))
      (node (ref "OUTPUT") (pin "9") (pinfunction "9_9") (pintype "passive"))
      (node (ref "OUTPUT") (pin "G1") (pinfunction "G1_G1") (pintype "passive"))
      (node (ref "OUTPUT") (pin "G2") (pinfunction "G2_G2") (pintype "passive"))
      (node (ref "Q1") (pin "2") (pinfunction "E_2") (pintype "passive"))
      (node (ref "R3") (pin "2") (pinfunction "2_2") (pintype "passive"))
      (node (ref "R45") (pin "1") (pinfunction "1_1") (pintype "passive"))
      (node (ref "R46") (pin "2") (pinfunction "2_2") (pintype "passive"))
      (node (ref "R5") (pin "2") (pinfunction "2_2") (pintype "passive"))
      (node (ref "R50") (pin "1") (pinfunction "1_1") (pintype "passive"))
      (node (ref "R58") (pin "1") (pinfunction "1_1") (pintype "passive"))
      (node (ref "R59") (pin "2") (pinfunction "2_2") (pintype "passive"))
      (node (ref "R6") (pin "2") (pinfunction "2_2") (pintype "passive"))
      (node (ref "R63") (pin "1") (pinfunction "1_1") (pintype "passive"))
      (node (ref "R71") (pin "1") (pinfunction "1_1") (pintype "passive"))
      (node (ref "R72") (pin "2") (pinfunction "2_2") (pintype "passive"))
      (node (ref "R76") (pin "1") (pinfunction "1_1") (pintype "passive"))
      (node (ref "R8") (pin "2") (pinfunction "2_2") (pintype "passive"))
      (node (ref "R84") (pin "1") (pinfunction "1_1") (pintype "passive"))
      (node (ref "R90") (pin "1") (pinfunction "1_1") (pintype "passive"))
      (node (ref "RS485-IN") (pin "3") (pinfunction "3_3") (pintype "passive"))
      (node (ref "RS485-IN") (pin "SH$1") (pinfunction "SH_SH$1") (pintype "passive"))
      (node (ref "RS485-IN") (pin "SH$2") (pinfunction "SH_SH$2") (pintype "passive"))
      (node (ref "RS485-OUT") (pin "3") (pinfunction "3_3") (pintype "passive"))
      (node (ref "RS485-OUT") (pin "SH$1") (pinfunction "SH_SH$1") (pintype "passive"))
      (node (ref "RS485-OUT") (pin "SH$2") (pinfunction "SH_SH$2") (pintype "passive"))
      (node (ref "S1") (pin "5") (pinfunction "5_5") (pintype "passive"))
      (node (ref "SJ1") (pin "1") (pinfunction "1_1") (pintype "passive"))
      (node (ref "U1") (pin "4") (pinfunction "COM_4") (pintype "passive"))
      (node (ref "U2") (pin "6") (pinfunction "-VOUT_6") (pintype "passive"))
      (node (ref "USB") (pin "GND") (pinfunction "4_GND") (pintype "bidirectional"))
      (node (ref "USB") (pin "P$1") (pinfunction "5_P$1") (pintype "bidirectional"))
      (node (ref "USB") (pin "P$2") (pinfunction "5_P$2") (pintype "bidirectional"))
      (node (ref "USB") (pin "P$3") (pinfunction "5_P$3") (pintype "bidirectional"))
      (node (ref "USB") (pin "P$4") (pinfunction "5_P$4") (pintype "bidirectional"))
      (node (ref "USB") (pin "P$5") (pinfunction "5_P$5") (pintype "bidirectional"))
    )
    (net (code "81") (name "H{slash}~{F}") (class "Default")
      (node (ref "IC13") (pin "1") (pinfunction "H/~{F}_1") (pintype "bidirectional"))
      (node (ref "S1") (pin "12") (pinfunction "12_12") (pintype "passive"))
    )
    (net (code "82") (name "LED_ERROR") (class "Default")
      (node (ref "IC11") (pin "60") (pinfunction "RPB10/PWM3H/PMPD0/RB10_60") (pintype "bidirectional"))
      (node (ref "R89") (pin "1") (pinfunction "1_1") (pintype "passive"))
    )
    (net (code "83") (name "LED_READY") (class "Default")
      (node (ref "IC11") (pin "58") (pinfunction "RPF0/PWM11H/RF0_58") (pintype "bidirectional"))
      (node (ref "R85") (pin "1") (pinfunction "1_1") (pintype "passive"))
    )
    (net (code "84") (name "LED_STATE") (class "Default")
      (node (ref "IC11") (pin "59") (pinfunction "RPF1/PWM11L/RF1_59") (pintype "bidirectional"))
      (node (ref "R88") (pin "1") (pinfunction "1_1") (pintype "passive"))
    )
    (net (code "85") (name "MSCK") (class "Default")
      (node (ref "IC10") (pin "6") (pinfunction "SCK_6") (pintype "bidirectional"))
      (node (ref "IC11") (pin "51") (pinfunction "TRD0/RPC7/PWM12H/PWM6L/RC7_51") (pintype "bidirectional"))
    )
    (net (code "86") (name "MSDI") (class "Default")
      (node (ref "IC10") (pin "2") (pinfunction "SO_2") (pintype "bidirectional"))
      (node (ref "IC11") (pin "48") (pinfunction "SOSCO/RPB8/RB8_48") (pintype "bidirectional"))
    )
    (net (code "87") (name "MSDO") (class "Default")
      (node (ref "IC10") (pin "5") (pinfunction "SI_5") (pintype "bidirectional"))
      (node (ref "IC11") (pin "49") (pinfunction "TMS/OA5IN-/AN27/CVD27/C5IN1-/RPB9/RB9_49") (pintype "bidirectional"))
    )
    (net (code "88") (name "Net-(C23-Pad2)") (class "Default")
      (node (ref "C23") (pin "2") (pinfunction "2_2") (pintype "passive"))
      (node (ref "R48") (pin "2") (pinfunction "2_2") (pintype "passive"))
      (node (ref "R49") (pin "1") (pinfunction "1_1") (pintype "passive"))
    )
    (net (code "89") (name "Net-(C25-Pad1)") (class "Default")
      (node (ref "C25") (pin "1") (pinfunction "1_1") (pintype "passive"))
      (node (ref "R55") (pin "2") (pinfunction "2_2") (pintype "passive"))
      (node (ref "R56") (pin "1") (pinfunction "1_1") (pintype "passive"))
    )
    (net (code "90") (name "Net-(C28-Pad2)") (class "Default")
      (node (ref "C28") (pin "2") (pinfunction "2_2") (pintype "passive"))
      (node (ref "R61") (pin "2") (pinfunction "2_2") (pintype "passive"))
      (node (ref "R62") (pin "1") (pinfunction "1_1") (pintype "passive"))
    )
    (net (code "91") (name "Net-(C30-Pad1)") (class "Default")
      (node (ref "C30") (pin "1") (pinfunction "1_1") (pintype "passive"))
      (node (ref "R68") (pin "2") (pinfunction "2_2") (pintype "passive"))
      (node (ref "R69") (pin "1") (pinfunction "1_1") (pintype "passive"))
    )
    (net (code "92") (name "Net-(C33-Pad2)") (class "Default")
      (node (ref "C33") (pin "2") (pinfunction "2_2") (pintype "passive"))
      (node (ref "R74") (pin "2") (pinfunction "2_2") (pintype "passive"))
      (node (ref "R75") (pin "1") (pinfunction "1_1") (pintype "passive"))
    )
    (net (code "93") (name "Net-(C35-Pad1)") (class "Default")
      (node (ref "C35") (pin "1") (pinfunction "1_1") (pintype "passive"))
      (node (ref "R81") (pin "2") (pinfunction "2_2") (pintype "passive"))
      (node (ref "R82") (pin "1") (pinfunction "1_1") (pintype "passive"))
    )
    (net (code "94") (name "Net-(C45-Pad2)") (class "Default")
      (node (ref "C45") (pin "2") (pinfunction "2_2") (pintype "passive"))
      (node (ref "R91") (pin "1") (pinfunction "1_1") (pintype "passive"))
      (node (ref "R92") (pin "1") (pinfunction "1_1") (pintype "passive"))
    )
    (net (code "95") (name "Net-(D1-A)") (class "Default")
      (node (ref "D1") (pin "1") (pinfunction "A_1") (pintype "passive"))
      (node (ref "K1") (pin "8") (pinfunction "-_8") (pintype "passive"))
      (node (ref "Q1") (pin "3") (pinfunction "C_3") (pintype "passive"))
    )
    (net (code "96") (name "Net-(D2-C)") (class "Default")
      (node (ref "D2") (pin "2") (pinfunction "C_2") (pintype "passive"))
      (node (ref "R10") (pin "1") (pinfunction "1_1") (pintype "passive"))
      (node (ref "R11") (pin "2") (pinfunction "2_2") (pintype "passive"))
    )
    (net (code "97") (name "Net-(D3-C)") (class "Default")
      (node (ref "D3") (pin "2") (pinfunction "C_2") (pintype "passive"))
      (node (ref "R12") (pin "1") (pinfunction "1_1") (pintype "passive"))
      (node (ref "R13") (pin "2") (pinfunction "2_2") (pintype "passive"))
    )
    (net (code "98") (name "Net-(IC6A-+IN)") (class "Default")
      (node (ref "C22") (pin "2") (pinfunction "2_2") (pintype "passive"))
      (node (ref "IC6") (pin "3") (pinfunction "+IN_3") (pintype "input"))
      (node (ref "R49") (pin "2") (pinfunction "2_2") (pintype "passive"))
    )
    (net (code "99") (name "Net-(IC6A--IN)") (class "Default")
      (node (ref "IC6") (pin "2") (pinfunction "-IN_2") (pintype "input"))
      (node (ref "R46") (pin "1") (pinfunction "1_1") (pintype "passive"))
      (node (ref "R47") (pin "2") (pinfunction "2_2") (pintype "passive"))
    )
    (net (code "100") (name "Net-(IC6A-OUT)") (class "Default")
      (node (ref "C23") (pin "1") (pinfunction "1_1") (pintype "passive"))
      (node (ref "IC6") (pin "1") (pinfunction "OUT_1") (pintype "output"))
      (node (ref "R47") (pin "1") (pinfunction "1_1") (pintype "passive"))
      (node (ref "R51") (pin "2") (pinfunction "2_2") (pintype "passive"))
    )
    (net (code "101") (name "Net-(IC6B-+IN)") (class "Default")
      (node (ref "C26") (pin "1") (pinfunction "1_1") (pintype "passive"))
      (node (ref "IC6") (pin "5") (pinfunction "+IN_5") (pintype "input"))
      (node (ref "R56") (pin "2") (pinfunction "2_2") (pintype "passive"))
    )
    (net (code "102") (name "Net-(IC6B--IN)") (class "Default")
      (node (ref "IC6") (pin "6") (pinfunction "-IN_6") (pintype "input"))
      (node (ref "R57") (pin "1") (pinfunction "1_1") (pintype "passive"))
      (node (ref "R58") (pin "2") (pinfunction "2_2") (pintype "passive"))
    )
    (net (code "103") (name "Net-(IC6B-OUT)") (class "Default")
      (node (ref "C25") (pin "2") (pinfunction "2_2") (pintype "passive"))
      (node (ref "IC6") (pin "7") (pinfunction "OUT_7") (pintype "output"))
      (node (ref "R53") (pin "2") (pinfunction "2_2") (pintype "passive"))
      (node (ref "R57") (pin "2") (pinfunction "2_2") (pintype "passive"))
    )
    (net (code "104") (name "Net-(IC6C-+IN)") (class "Default")
      (node (ref "IC6") (pin "10") (pinfunction "+IN_10") (pintype "input"))
      (node (ref "R50") (pin "2") (pinfunction "2_2") (pintype "passive"))
      (node (ref "R51") (pin "1") (pinfunction "1_1") (pintype "passive"))
    )
    (net (code "105") (name "Net-(IC6C--IN)") (class "Default")
      (node (ref "IC6") (pin "9") (pinfunction "-IN_9") (pintype "input"))
      (node (ref "R53") (pin "1") (pinfunction "1_1") (pintype "passive"))
      (node (ref "R54") (pin "1") (pinfunction "1_1") (pintype "passive"))
    )
    (net (code "106") (name "Net-(IC6C-OUT)") (class "Default")
      (node (ref "IC6") (pin "8") (pinfunction "OUT_8") (pintype "output"))
      (node (ref "R52") (pin "1") (pinfunction "1_1") (pintype "passive"))
      (node (ref "R54") (pin "2") (pinfunction "2_2") (pintype "passive"))
    )
    (net (code "107") (name "Net-(IC6D-+IN)") (class "Default")
      (node (ref "C24") (pin "1") (pinfunction "1_1") (pintype "passive"))
      (node (ref "IC6") (pin "12") (pinfunction "+IN_12") (pintype "input"))
      (node (ref "R52") (pin "2") (pinfunction "2_2") (pintype "passive"))
    )
    (net (code "108") (name "Net-(IC7A-+IN)") (class "Default")
      (node (ref "C27") (pin "2") (pinfunction "2_2") (pintype "passive"))
      (node (ref "IC7") (pin "3") (pinfunction "+IN_3") (pintype "input"))
      (node (ref "R62") (pin "2") (pinfunction "2_2") (pintype "passive"))
    )
    (net (code "109") (name "Net-(IC7A--IN)") (class "Default")
      (node (ref "IC7") (pin "2") (pinfunction "-IN_2") (pintype "input"))
      (node (ref "R59") (pin "1") (pinfunction "1_1") (pintype "passive"))
      (node (ref "R60") (pin "2") (pinfunction "2_2") (pintype "passive"))
    )
    (net (code "110") (name "Net-(IC7A-OUT)") (class "Default")
      (node (ref "C28") (pin "1") (pinfunction "1_1") (pintype "passive"))
      (node (ref "IC7") (pin "1") (pinfunction "OUT_1") (pintype "output"))
      (node (ref "R60") (pin "1") (pinfunction "1_1") (pintype "passive"))
      (node (ref "R64") (pin "2") (pinfunction "2_2") (pintype "passive"))
    )
    (net (code "111") (name "Net-(IC7B-+IN)") (class "Default")
      (node (ref "C31") (pin "1") (pinfunction "1_1") (pintype "passive"))
      (node (ref "IC7") (pin "5") (pinfunction "+IN_5") (pintype "input"))
      (node (ref "R69") (pin "2") (pinfunction "2_2") (pintype "passive"))
    )
    (net (code "112") (name "Net-(IC7B--IN)") (class "Default")
      (node (ref "IC7") (pin "6") (pinfunction "-IN_6") (pintype "input"))
      (node (ref "R70") (pin "1") (pinfunction "1_1") (pintype "passive"))
      (node (ref "R71") (pin "2") (pinfunction "2_2") (pintype "passive"))
    )
    (net (code "113") (name "Net-(IC7B-OUT)") (class "Default")
      (node (ref "C30") (pin "2") (pinfunction "2_2") (pintype "passive"))
      (node (ref "IC7") (pin "7") (pinfunction "OUT_7") (pintype "output"))
      (node (ref "R66") (pin "2") (pinfunction "2_2") (pintype "passive"))
      (node (ref "R70") (pin "2") (pinfunction "2_2") (pintype "passive"))
    )
    (net (code "114") (name "Net-(IC7C-+IN)") (class "Default")
      (node (ref "IC7") (pin "10") (pinfunction "+IN_10") (pintype "input"))
      (node (ref "R63") (pin "2") (pinfunction "2_2") (pintype "passive"))
      (node (ref "R64") (pin "1") (pinfunction "1_1") (pintype "passive"))
    )
    (net (code "115") (name "Net-(IC7C--IN)") (class "Default")
      (node (ref "IC7") (pin "9") (pinfunction "-IN_9") (pintype "input"))
      (node (ref "R66") (pin "1") (pinfunction "1_1") (pintype "passive"))
      (node (ref "R67") (pin "1") (pinfunction "1_1") (pintype "passive"))
    )
    (net (code "116") (name "Net-(IC7C-OUT)") (class "Default")
      (node (ref "IC7") (pin "8") (pinfunction "OUT_8") (pintype "output"))
      (node (ref "R65") (pin "1") (pinfunction "1_1") (pintype "passive"))
      (node (ref "R67") (pin "2") (pinfunction "2_2") (pintype "passive"))
    )
    (net (code "117") (name "Net-(IC7D-+IN)") (class "Default")
      (node (ref "C29") (pin "1") (pinfunction "1_1") (pintype "passive"))
      (node (ref "IC7") (pin "12") (pinfunction "+IN_12") (pintype "input"))
      (node (ref "R65") (pin "2") (pinfunction "2_2") (pintype "passive"))
    )
    (net (code "118") (name "Net-(IC8A-+IN)") (class "Default")
      (node (ref "C32") (pin "2") (pinfunction "2_2") (pintype "passive"))
      (node (ref "IC8") (pin "3") (pinfunction "+IN_3") (pintype "input"))
      (node (ref "R75") (pin "2") (pinfunction "2_2") (pintype "passive"))
    )
    (net (code "119") (name "Net-(IC8A--IN)") (class "Default")
      (node (ref "IC8") (pin "2") (pinfunction "-IN_2") (pintype "input"))
      (node (ref "R72") (pin "1") (pinfunction "1_1") (pintype "passive"))
      (node (ref "R73") (pin "2") (pinfunction "2_2") (pintype "passive"))
    )
    (net (code "120") (name "Net-(IC8A-OUT)") (class "Default")
      (node (ref "C33") (pin "1") (pinfunction "1_1") (pintype "passive"))
      (node (ref "IC8") (pin "1") (pinfunction "OUT_1") (pintype "output"))
      (node (ref "R73") (pin "1") (pinfunction "1_1") (pintype "passive"))
      (node (ref "R77") (pin "2") (pinfunction "2_2") (pintype "passive"))
    )
    (net (code "121") (name "Net-(IC8B-+IN)") (class "Default")
      (node (ref "C36") (pin "1") (pinfunction "1_1") (pintype "passive"))
      (node (ref "IC8") (pin "5") (pinfunction "+IN_5") (pintype "input"))
      (node (ref "R82") (pin "2") (pinfunction "2_2") (pintype "passive"))
    )
    (net (code "122") (name "Net-(IC8B--IN)") (class "Default")
      (node (ref "IC8") (pin "6") (pinfunction "-IN_6") (pintype "input"))
      (node (ref "R83") (pin "1") (pinfunction "1_1") (pintype "passive"))
      (node (ref "R84") (pin "2") (pinfunction "2_2") (pintype "passive"))
    )
    (net (code "123") (name "Net-(IC8B-OUT)") (class "Default")
      (node (ref "C35") (pin "2") (pinfunction "2_2") (pintype "passive"))
      (node (ref "IC8") (pin "7") (pinfunction "OUT_7") (pintype "output"))
      (node (ref "R79") (pin "2") (pinfunction "2_2") (pintype "passive"))
      (node (ref "R83") (pin "2") (pinfunction "2_2") (pintype "passive"))
    )
    (net (code "124") (name "Net-(IC8C-+IN)") (class "Default")
      (node (ref "IC8") (pin "10") (pinfunction "+IN_10") (pintype "input"))
      (node (ref "R76") (pin "2") (pinfunction "2_2") (pintype "passive"))
      (node (ref "R77") (pin "1") (pinfunction "1_1") (pintype "passive"))
    )
    (net (code "125") (name "Net-(IC8C--IN)") (class "Default")
      (node (ref "IC8") (pin "9") (pinfunction "-IN_9") (pintype "input"))
      (node (ref "R79") (pin "1") (pinfunction "1_1") (pintype "passive"))
      (node (ref "R80") (pin "1") (pinfunction "1_1") (pintype "passive"))
    )
    (net (code "126") (name "Net-(IC8C-OUT)") (class "Default")
      (node (ref "IC8") (pin "8") (pinfunction "OUT_8") (pintype "output"))
      (node (ref "R78") (pin "1") (pinfunction "1_1") (pintype "passive"))
      (node (ref "R80") (pin "2") (pinfunction "2_2") (pintype "passive"))
    )
    (net (code "127") (name "Net-(IC8D-+IN)") (class "Default")
      (node (ref "C34") (pin "1") (pinfunction "1_1") (pintype "passive"))
      (node (ref "IC8") (pin "12") (pinfunction "+IN_12") (pintype "input"))
      (node (ref "R78") (pin "2") (pinfunction "2_2") (pintype "passive"))
    )
    (net (code "128") (name "Net-(IC10-~{HOLD})") (class "Default")
      (node (ref "IC10") (pin "7") (pinfunction "~{HOLD}_7") (pintype "bidirectional"))
      (node (ref "R87") (pin "2") (pinfunction "2_2") (pintype "passive"))
    )
    (net (code "129") (name "Net-(L1-2)") (class "Default")
      (node (ref "C1") (pin "1") (pinfunction "1_1") (pintype "passive"))
      (node (ref "L1") (pin "B") (pinfunction "2_B") (pintype "passive"))
      (node (ref "U1") (pin "1") (pinfunction "+VIN_1") (pintype "passive"))
    )
    (net (code "130") (name "Net-(L2-2)") (class "Default")
      (node (ref "C8") (pin "1") (pinfunction "1_1") (pintype "passive"))
      (node (ref "L2") (pin "B") (pinfunction "2_B") (pintype "passive"))
      (node (ref "U2") (pin "1") (pinfunction "+VIN_1") (pintype "passive"))
    )
    (net (code "131") (name "Net-(LED1-AG)") (class "Default")
      (node (ref "LED1") (pin "AX") (pinfunction "AG_AX") (pintype "passive"))
      (node (ref "R11") (pin "1") (pinfunction "1_1") (pintype "passive"))
    )
    (net (code "132") (name "Net-(LED2-AG)") (class "Default")
      (node (ref "LED2") (pin "AX") (pinfunction "AG_AX") (pintype "passive"))
      (node (ref "R13") (pin "1") (pinfunction "1_1") (pintype "passive"))
    )
    (net (code "133") (name "Net-(LED3-PadC)") (class "Default")
      (node (ref "LED3") (pin "C") (pinfunction "C_C") (pintype "passive"))
      (node (ref "R3") (pin "1") (pinfunction "1_1") (pintype "passive"))
    )
    (net (code "134") (name "Net-(LED5-PadA)") (class "Default")
      (node (ref "LED5") (pin "A") (pinfunction "A_A") (pintype "passive"))
      (node (ref "R5") (pin "1") (pinfunction "1_1") (pintype "passive"))
    )
    (net (code "135") (name "Net-(LED6-PadC)") (class "Default")
      (node (ref "LED6") (pin "C") (pinfunction "C_C") (pintype "passive"))
      (node (ref "R6") (pin "1") (pinfunction "1_1") (pintype "passive"))
    )
    (net (code "136") (name "Net-(LED8-PadC)") (class "Default")
      (node (ref "LED8") (pin "C") (pinfunction "C_C") (pintype "passive"))
      (node (ref "R8") (pin "1") (pinfunction "1_1") (pintype "passive"))
    )
    (net (code "137") (name "Net-(LED14-PadA)") (class "Default")
      (node (ref "LED14") (pin "A") (pinfunction "A_A") (pintype "passive"))
      (node (ref "R85") (pin "2") (pinfunction "2_2") (pintype "passive"))
    )
    (net (code "138") (name "Net-(LED15-PadA)") (class "Default")
      (node (ref "LED15") (pin "A") (pinfunction "A_A") (pintype "passive"))
      (node (ref "R88") (pin "2") (pinfunction "2_2") (pintype "passive"))
    )
    (net (code "139") (name "Net-(LED16-PadA)") (class "Default")
      (node (ref "LED16") (pin "A") (pinfunction "A_A") (pintype "passive"))
      (node (ref "R89") (pin "2") (pinfunction "2_2") (pintype "passive"))
    )
    (net (code "140") (name "Net-(LED19-PadA)") (class "Default")
      (node (ref "LED19") (pin "A") (pinfunction "A_A") (pintype "passive"))
      (node (ref "R95") (pin "2") (pinfunction "2_2") (pintype "passive"))
    )
    (net (code "141") (name "Net-(LED20-PadA)") (class "Default")
      (node (ref "LED20") (pin "A") (pinfunction "A_A") (pintype "passive"))
      (node (ref "R96") (pin "2") (pinfunction "2_2") (pintype "passive"))
    )
    (net (code "142") (name "Net-(OK1A-AC1)") (class "Default")
      (node (ref "C15") (pin "1") (pinfunction "1_1") (pintype "passive"))
      (node (ref "OK1") (pin "1") (pinfunction "AC1_1") (pintype "passive"))
      (node (ref "R15") (pin "2") (pinfunction "2_2") (pintype "passive"))
    )
    (net (code "143") (name "Net-(OK1B-AC1)") (class "Default")
      (node (ref "C16") (pin "1") (pinfunction "1_1") (pintype "passive"))
      (node (ref "OK1") (pin "3") (pinfunction "AC1_3") (pintype "passive"))
      (node (ref "R17") (pin "2") (pinfunction "2_2") (pintype "passive"))
    )
    (net (code "144") (name "Net-(OK1C-AC1)") (class "Default")
      (node (ref "C17") (pin "1") (pinfunction "1_1") (pintype "passive"))
      (node (ref "OK1") (pin "5") (pinfunction "AC1_5") (pintype "passive"))
      (node (ref "R19") (pin "2") (pinfunction "2_2") (pintype "passive"))
    )
    (net (code "145") (name "Net-(OK1D-AC1)") (class "Default")
      (node (ref "C18") (pin "1") (pinfunction "1_1") (pintype "passive"))
      (node (ref "OK1") (pin "7") (pinfunction "AC1_7") (pintype "passive"))
      (node (ref "R22") (pin "2") (pinfunction "2_2") (pintype "passive"))
    )
    (net (code "146") (name "Net-(OK2A-A)") (class "Default")
      (node (ref "OK2") (pin "1") (pinfunction "A_1") (pintype "passive"))
      (node (ref "R25") (pin "2") (pinfunction "2_2") (pintype "passive"))
    )
    (net (code "147") (name "Net-(OK2B-A)") (class "Default")
      (node (ref "OK2") (pin "4") (pinfunction "A_4") (pintype "passive"))
      (node (ref "R29") (pin "2") (pinfunction "2_2") (pintype "passive"))
    )
    (net (code "148") (name "Net-(OK3A-A)") (class "Default")
      (node (ref "OK3") (pin "1") (pinfunction "A_1") (pintype "passive"))
      (node (ref "R26") (pin "2") (pinfunction "2_2") (pintype "passive"))
    )
    (net (code "149") (name "Net-(OK3B-A)") (class "Default")
      (node (ref "OK3") (pin "4") (pinfunction "A_4") (pintype "passive"))
      (node (ref "R30") (pin "2") (pinfunction "2_2") (pintype "passive"))
    )
    (net (code "150") (name "Net-(OK4A-A)") (class "Default")
      (node (ref "OK4") (pin "1") (pinfunction "A_1") (pintype "passive"))
      (node (ref "R32") (pin "2") (pinfunction "2_2") (pintype "passive"))
    )
    (net (code "151") (name "Net-(OK4B-A)") (class "Default")
      (node (ref "OK4") (pin "4") (pinfunction "A_4") (pintype "passive"))
      (node (ref "R34") (pin "2") (pinfunction "2_2") (pintype "passive"))
    )
    (net (code "152") (name "Net-(POWERA-KL)") (class "Default")
      (node (ref "F1") (pin "1") (pinfunction "1_1") (pintype "passive"))
      (node (ref "F2") (pin "1") (pinfunction "1_1") (pintype "passive"))
      (node (ref "POWER") (pin "1") (pinfunction "KL_1") (pintype "passive"))
      (node (ref "R2") (pin "1") (pinfunction "1_1") (pintype "passive"))
      (node (ref "R9") (pin "1") (pinfunction "1_1") (pintype "passive"))
    )
    (net (code "153") (name "Net-(Q1-B)") (class "Default")
      (node (ref "Q1") (pin "1") (pinfunction "B_1") (pintype "passive"))
      (node (ref "R20") (pin "2") (pinfunction "2_2") (pintype "passive"))
    )
    (net (code "154") (name "Net-(Q3-B)") (class "Default")
      (node (ref "Q3") (pin "1") (pinfunction "B_1") (pintype "passive"))
      (node (ref "R10") (pin "2") (pinfunction "2_2") (pintype "passive"))
    )
    (net (code "155") (name "Net-(Q3-C)") (class "Default")
      (node (ref "LED1") (pin "AR") (pinfunction "AR_AR") (pintype "passive"))
      (node (ref "Q3") (pin "3") (pinfunction "C_3") (pintype "passive"))
      (node (ref "R9") (pin "2") (pinfunction "2_2") (pintype "passive"))
    )
    (net (code "156") (name "Net-(Q4-B)") (class "Default")
      (node (ref "Q4") (pin "1") (pinfunction "B_1") (pintype "passive"))
      (node (ref "R12") (pin "2") (pinfunction "2_2") (pintype "passive"))
    )
    (net (code "157") (name "Net-(Q4-C)") (class "Default")
      (node (ref "LED2") (pin "AR") (pinfunction "AR_AR") (pintype "passive"))
      (node (ref "Q4") (pin "3") (pinfunction "C_3") (pintype "passive"))
      (node (ref "R2") (pin "2") (pinfunction "2_2") (pintype "passive"))
    )
    (net (code "158") (name "Net-(R97-Pad1)") (class "Default")
      (node (ref "R97") (pin "1") (pinfunction "1_1") (pintype "passive"))
      (node (ref "S1") (pin "9") (pinfunction "9_9") (pintype "passive"))
    )
    (net (code "159") (name "OSC1I") (class "Default")
      (node (ref "C43") (pin "2") (pinfunction "2_2") (pintype "passive"))
      (node (ref "IC11") (pin "39") (pinfunction "OSCI/CLKI/AN49/CVD49/RPC12/RC12_39") (pintype "bidirectional"))
      (node (ref "Q2") (pin "2") (pinfunction "2_2") (pintype "passive"))
    )
    (net (code "160") (name "OSC1O") (class "Default")
      (node (ref "C44") (pin "2") (pinfunction "2_2") (pintype "passive"))
      (node (ref "IC11") (pin "40") (pinfunction "OSCO/CLKO/RPC15/RC15_40") (pintype "bidirectional"))
      (node (ref "Q2") (pin "1") (pinfunction "1_1") (pintype "passive"))
    )
    (net (code "161") (name "PGEC") (class "Default")
      (node (ref "IC11") (pin "44") (pinfunction "PGEC2/RPB6/SCK2/PMPA15/RB6_44") (pintype "bidirectional"))
      (node (ref "ICSP") (pin "5") (pinfunction "5_5") (pintype "passive"))
    )
    (net (code "162") (name "PGED") (class "Default")
      (node (ref "IC11") (pin "43") (pinfunction "PGED2/RPB5/USBID1/RB5_43") (pintype "bidirectional"))
      (node (ref "ICSP") (pin "4") (pinfunction "4_4") (pintype "passive"))
    )
    (net (code "163") (name "REF") (class "Default")
      (node (ref "R44") (pin "1") (pinfunction "1_1") (pintype "passive"))
      (node (ref "R45") (pin "2") (pinfunction "2_2") (pintype "passive"))
      (node (ref "SJ10") (pin "1") (pinfunction "1_1") (pintype "passive"))
      (node (ref "SJ2") (pin "1") (pinfunction "1_1") (pintype "passive"))
      (node (ref "SJ3") (pin "1") (pinfunction "1_1") (pintype "passive"))
      (node (ref "SJ4") (pin "1") (pinfunction "1_1") (pintype "passive"))
      (node (ref "SJ5") (pin "1") (pinfunction "1_1") (pintype "passive"))
      (node (ref "SJ6") (pin "1") (pinfunction "1_1") (pintype "passive"))
      (node (ref "SJ7") (pin "1") (pinfunction "1_1") (pintype "passive"))
      (node (ref "SJ8") (pin "1") (pinfunction "1_1") (pintype "passive"))
      (node (ref "SJ9") (pin "1") (pinfunction "1_1") (pintype "passive"))
    )
    (net (code "164") (name "RO1") (class "Default")
      (node (ref "IC11") (pin "61") (pinfunction "RPB11/PWM9H/PWM3L/PMPD1/RB11_61") (pintype "bidirectional"))
      (node (ref "R20") (pin "1") (pinfunction "1_1") (pintype "passive"))
    )
    (net (code "165") (name "RO1_COM_CON") (class "Default")
      (node (ref "K1") (pin "3") (pinfunction "P_3") (pintype "passive"))
      (node (ref "READY") (pin "2") (pinfunction "KL_2") (pintype "passive"))
    )
    (net (code "166") (name "RO1_NC_CON") (class "Default")
      (node (ref "K1") (pin "2") (pinfunction "O_2") (pintype "passive"))
      (node (ref "READY") (pin "3") (pinfunction "KL_3") (pintype "passive"))
    )
    (net (code "167") (name "RO1_NO_CON") (class "Default")
      (node (ref "K1") (pin "4") (pinfunction "S_4") (pintype "passive"))
      (node (ref "READY") (pin "1") (pinfunction "KL_1") (pintype "passive"))
    )
    (net (code "168") (name "RS485_A") (class "Default")
      (node (ref "IC13") (pin "12") (pinfunction "A_12") (pintype "input"))
      (node (ref "RS485-IN") (pin "5") (pinfunction "5_5") (pintype "passive"))
      (node (ref "RS485-OUT") (pin "5") (pinfunction "5_5") (pintype "passive"))
    )
    (net (code "169") (name "RS485_B") (class "Default")
      (node (ref "IC13") (pin "11") (pinfunction "B_11") (pintype "input"))
      (node (ref "RS485-IN") (pin "8") (pinfunction "8_8") (pintype "passive"))
      (node (ref "RS485-OUT") (pin "8") (pinfunction "8_8") (pintype "passive"))
    )
    (net (code "170") (name "RS485_Y") (class "Default")
      (node (ref "IC13") (pin "9") (pinfunction "Y_9") (pintype "output"))
      (node (ref "RS485-IN") (pin "1") (pinfunction "1_1") (pintype "passive"))
      (node (ref "RS485-OUT") (pin "1") (pinfunction "1_1") (pintype "passive"))
    )
    (net (code "171") (name "RS485_Z") (class "Default")
      (node (ref "IC13") (pin "10") (pinfunction "Z_10") (pintype "output"))
      (node (ref "RS485-IN") (pin "4") (pinfunction "4_4") (pintype "passive"))
      (node (ref "RS485-OUT") (pin "4") (pinfunction "4_4") (pintype "passive"))
    )
    (net (code "172") (name "RXP") (class "Default")
      (node (ref "IC13") (pin "13") (pinfunction "RXP_13") (pintype "passive"))
      (node (ref "S1") (pin "10") (pinfunction "10_10") (pintype "passive"))
    )
    (net (code "173") (name "SLR") (class "Default")
      (node (ref "IC13") (pin "6") (pinfunction "SLR_6") (pintype "bidirectional"))
      (node (ref "R97") (pin "2") (pinfunction "2_2") (pintype "passive"))
      (node (ref "S1") (pin "8") (pinfunction "8_8") (pintype "passive"))
    )
    (net (code "174") (name "TXP") (class "Default")
      (node (ref "IC13") (pin "8") (pinfunction "TXP_8") (pintype "passive"))
      (node (ref "S1") (pin "11") (pinfunction "11_11") (pintype "passive"))
    )
    (net (code "175") (name "UART_RX") (class "Default")
      (node (ref "IC11") (pin "55") (pinfunction "RPC9/PWM11H/PWM5L/RC9_55") (pintype "bidirectional"))
      (node (ref "IC13") (pin "2") (pinfunction "RO_2") (pintype "output"))
      (node (ref "LED20") (pin "C") (pinfunction "C_C") (pintype "passive"))
    )
    (net (code "176") (name "UART_TX") (class "Default")
      (node (ref "IC11") (pin "54") (pinfunction "TRD3/RPD6/PWM12L/RD6_54") (pintype "bidirectional"))
      (node (ref "IC13") (pin "5") (pinfunction "DI_5") (pintype "input"))
      (node (ref "LED19") (pin "C") (pinfunction "C_C") (pintype "passive"))
    )
    (net (code "177") (name "UART_~{CTS}") (class "Default")
      (node (ref "IC11") (pin "46") (pinfunction "OA5OUT/AN25/CVD25/C5IN4-/RPB7/SCK1/INT0/RB7_46") (pintype "bidirectional"))
      (node (ref "IC13") (pin "3") (pinfunction "~{RE}_3") (pintype "input"))
      (node (ref "IC13") (pin "4") (pinfunction "DE_4") (pintype "input"))
    )
    (net (code "178") (name "UART_~{RTR}") (class "Default")
      (node (ref "IC11") (pin "45") (pinfunction "DAC2/AN48/CVD48/RPC10/PMPA14/PSPCS/RC10_45") (pintype "bidirectional"))
    )
    (net (code "179") (name "USB_D+") (class "Default")
      (node (ref "IC11") (pin "37") (pinfunction "D+_37") (pintype "bidirectional"))
      (node (ref "USB") (pin "D+") (pinfunction "1_D+") (pintype "bidirectional"))
    )
    (net (code "180") (name "USB_D-") (class "Default")
      (node (ref "IC11") (pin "36") (pinfunction "D-_36") (pintype "bidirectional"))
      (node (ref "USB") (pin "D-") (pinfunction "2_D-") (pintype "bidirectional"))
    )
    (net (code "181") (name "VBUS") (class "Default")
      (node (ref "IC11") (pin "34") (pinfunction "VBUS_34") (pintype "bidirectional"))
      (node (ref "USB") (pin "VBUS") (pinfunction "3_VBUS") (pintype "bidirectional"))
    )
    (net (code "182") (name "unconnected-(IC11-AN12{slash}CVD12{slash}C2IN2-{slash}C5IN2-{slash}FLT5{slash}PMPA11{slash}RE12-Pad27)") (class "Default")
      (node (ref "IC11") (pin "27") (pinfunction "AN12/CVD12/C2IN2-/C5IN2-/FLT5/PMPA11/RE12_27") (pintype "input"))
    )
    (net (code "183") (name "unconnected-(IC11-AN13{slash}CVD13{slash}C3IN2-{slash}FLT6{slash}PMPA10{slash}RE13-Pad28)") (class "Default")
      (node (ref "IC11") (pin "28") (pinfunction "AN13/CVD13/C3IN2-/FLT6/PMPA10/RE13_28") (pintype "input"))
    )
    (net (code "184") (name "unconnected-(IC11-RD8-Pad42)") (class "Default")
      (node (ref "IC11") (pin "42") (pinfunction "RD8_42") (pintype "bidirectional"))
    )
    (net (code "185") (name "unconnected-(INTERFACE-Pad15)") (class "Default")
      (node (ref "INTERFACE") (pin "15") (pinfunction "15_15") (pintype "passive"))
    )
    (net (code "186") (name "unconnected-(K1C-O-Pad7)") (class "Default")
      (node (ref "K1") (pin "7") (pinfunction "O_7") (pintype "passive"))
    )
    (net (code "187") (name "unconnected-(K1C-P-Pad6)") (class "Default")
      (node (ref "K1") (pin "6") (pinfunction "P_6") (pintype "passive"))
    )
    (net (code "188") (name "unconnected-(K1C-S-Pad5)") (class "Default")
      (node (ref "K1") (pin "5") (pinfunction "S_5") (pintype "passive"))
    )
    (net (code "189") (name "unconnected-(RS485-IN-Pad2)") (class "Default")
      (node (ref "RS485-IN") (pin "2") (pinfunction "2_2") (pintype "passive"))
    )
    (net (code "190") (name "unconnected-(RS485-IN-Pad6)") (class "Default")
      (node (ref "RS485-IN") (pin "6") (pinfunction "6_6") (pintype "passive"))
    )
    (net (code "191") (name "unconnected-(RS485-IN-Pad7)") (class "Default")
      (node (ref "RS485-IN") (pin "7") (pinfunction "7_7") (pintype "passive"))
    )
    (net (code "192") (name "unconnected-(RS485-OUT-Pad2)") (class "Default")
      (node (ref "RS485-OUT") (pin "2") (pinfunction "2_2") (pintype "passive"))
    )
    (net (code "193") (name "unconnected-(RS485-OUT-Pad6)") (class "Default")
      (node (ref "RS485-OUT") (pin "6") (pinfunction "6_6") (pintype "passive"))
    )
    (net (code "194") (name "unconnected-(RS485-OUT-Pad7)") (class "Default")
      (node (ref "RS485-OUT") (pin "7") (pinfunction "7_7") (pintype "passive"))
    )
    (net (code "195") (name "unconnected-(S1-Pad6)") (class "Default")
      (node (ref "S1") (pin "6") (pinfunction "6_6") (pintype "passive"))
    )
    (net (code "196") (name "unconnected-(S1-Pad7)") (class "Default")
      (node (ref "S1") (pin "7") (pinfunction "7_7") (pintype "passive"))
    )
    (net (code "197") (name "unconnected-(U2-ON{slash}OFF-Pad3)") (class "Default")
      (node (ref "U2") (pin "3") (pinfunction "ON/OFF_3") (pintype "passive"))
    )
    (net (code "198") (name "~{MCLR}") (class "Default")
      (node (ref "IC11") (pin "7") (pinfunction "~{MCLR}_7") (pintype "input"))
      (node (ref "ICSP") (pin "1") (pinfunction "1_1") (pintype "passive"))
      (node (ref "R92") (pin "2") (pinfunction "2_2") (pintype "passive"))
    )
    (net (code "199") (name "~{MSS}") (class "Default")
      (node (ref "IC10") (pin "1") (pinfunction "~{CS}_1") (pintype "bidirectional"))
      (node (ref "IC11") (pin "50") (pinfunction "TRCLK/RPC6/PWM6H/RC6_50") (pintype "bidirectional"))
      (node (ref "R86") (pin "2") (pinfunction "2_2") (pintype "passive"))
    )
    (net (code "200") (name "~{MWP}") (class "Default")
      (node (ref "IC10") (pin "3") (pinfunction "~{WP}_3") (pintype "bidirectional"))
      (node (ref "IC11") (pin "47") (pinfunction "SOSCI/RPC13/RC13_47") (pintype "bidirectional"))
      (node (ref "R90") (pin "2") (pinfunction "2_2") (pintype "passive"))
    )
  )
)
